# MainBoard-20221122.net
KiCad netlist of a schematic drawn in Altium Designer
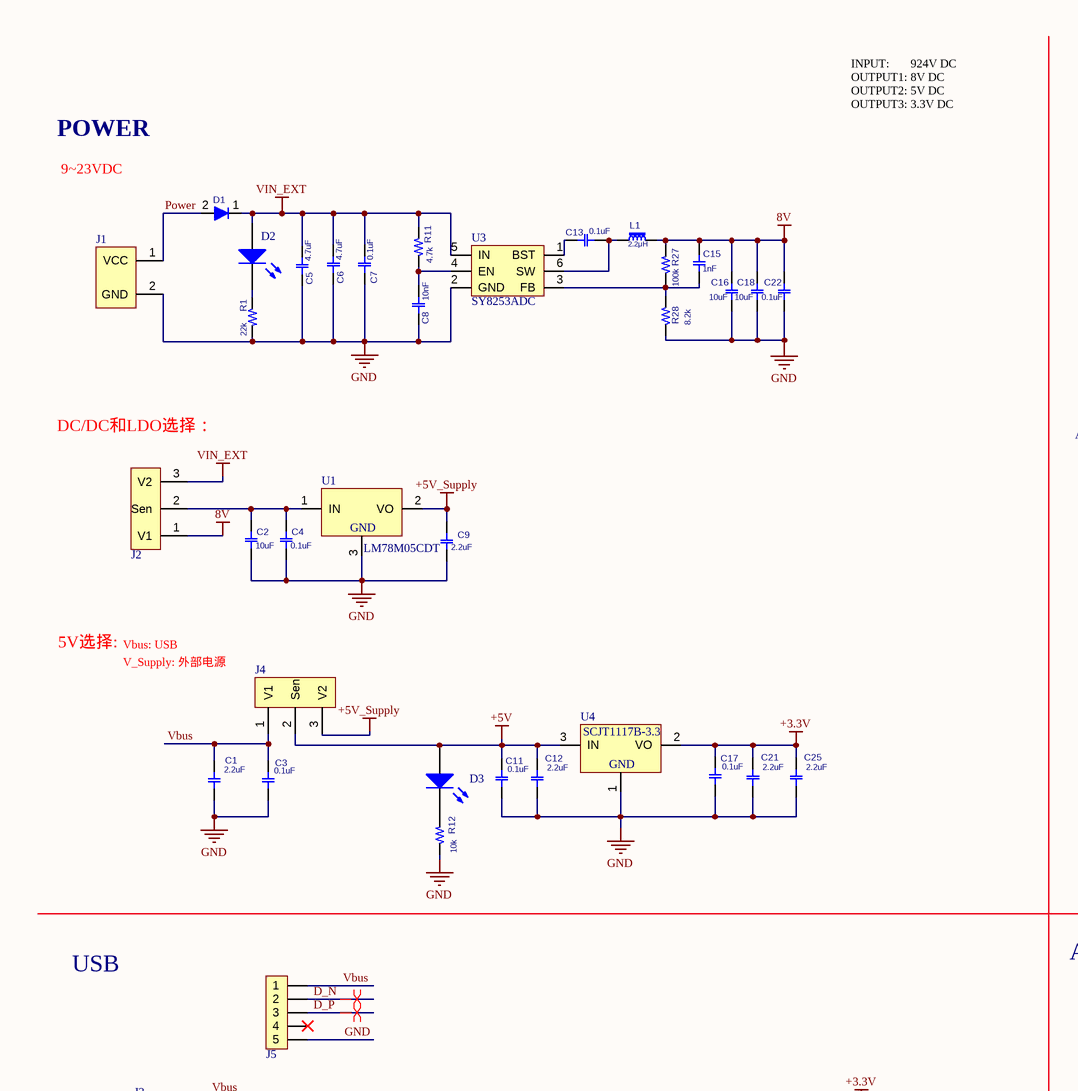
[diagram p0: MainBoard-20221122.SchDoc, top left]
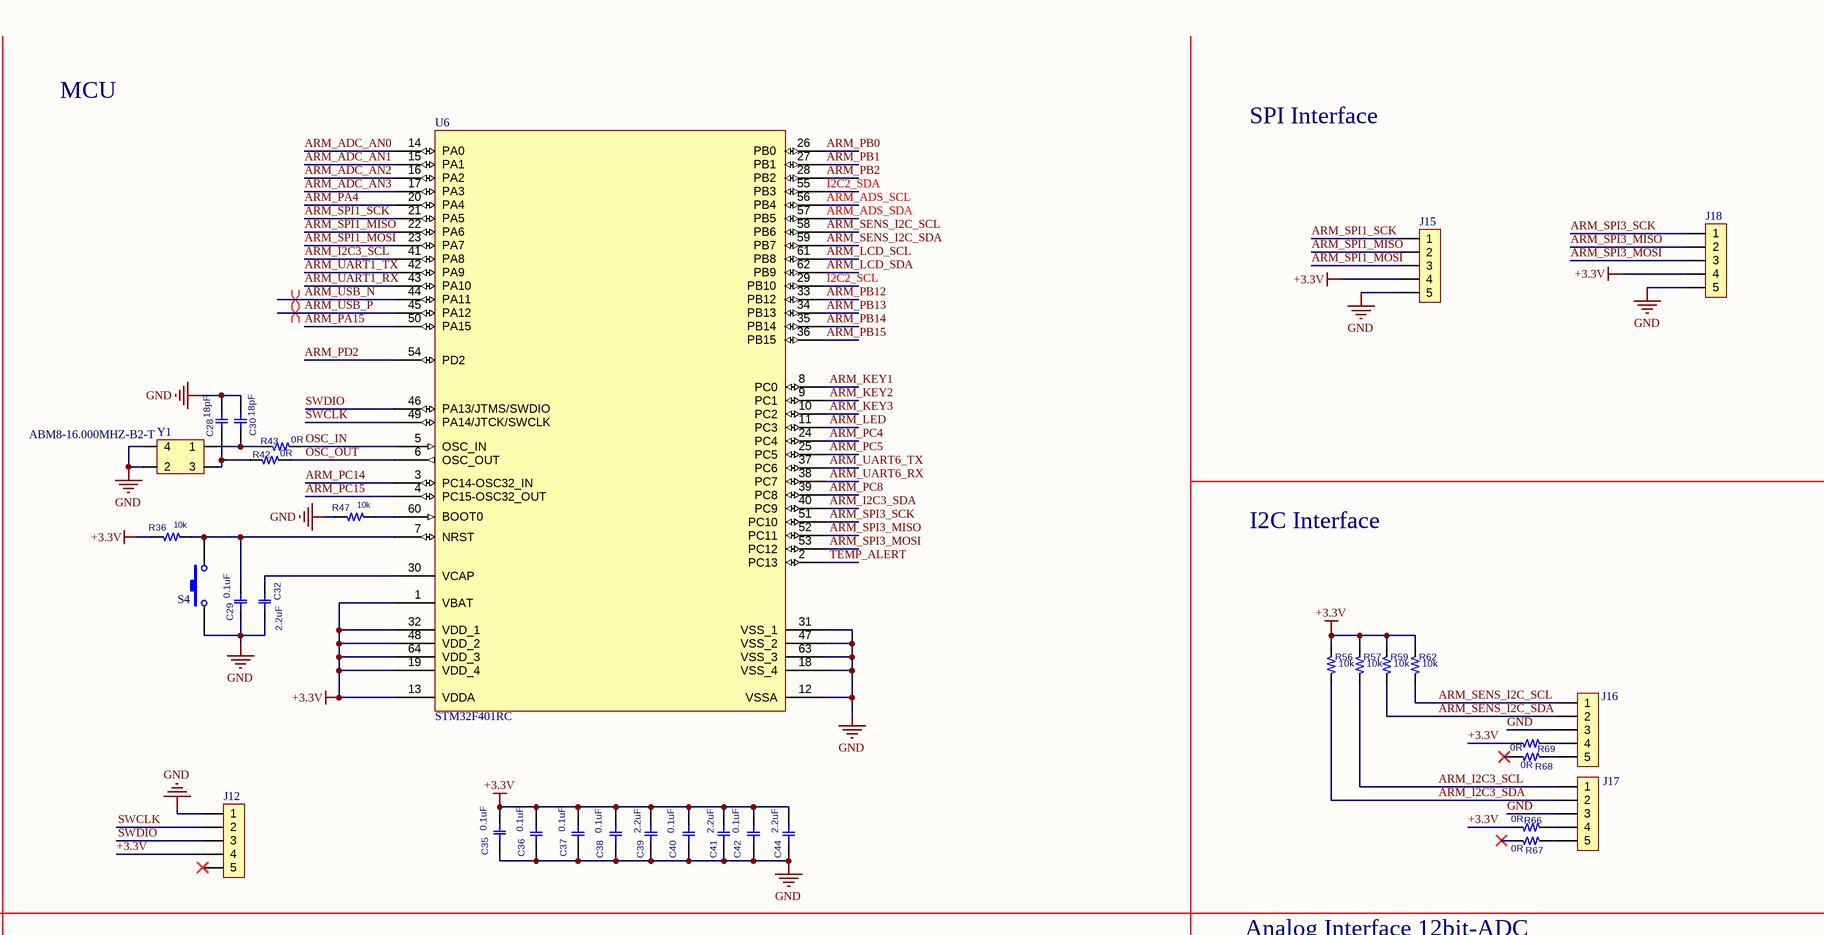
[diagram p1: MainBoard-20221122.SchDoc, top right]
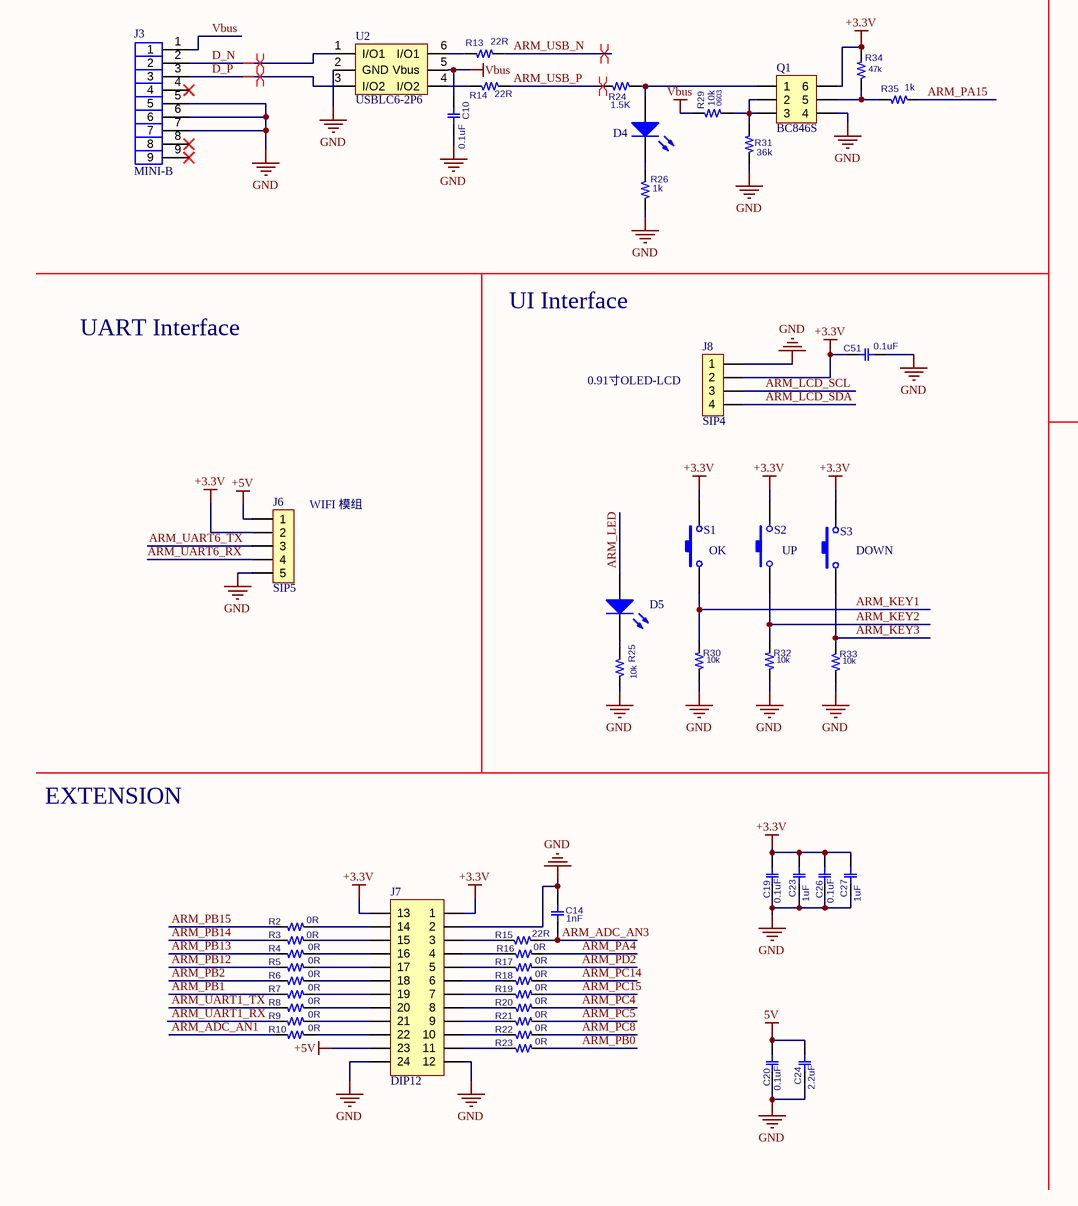
[diagram p2: MainBoard-20221122.SchDoc, bottom left]
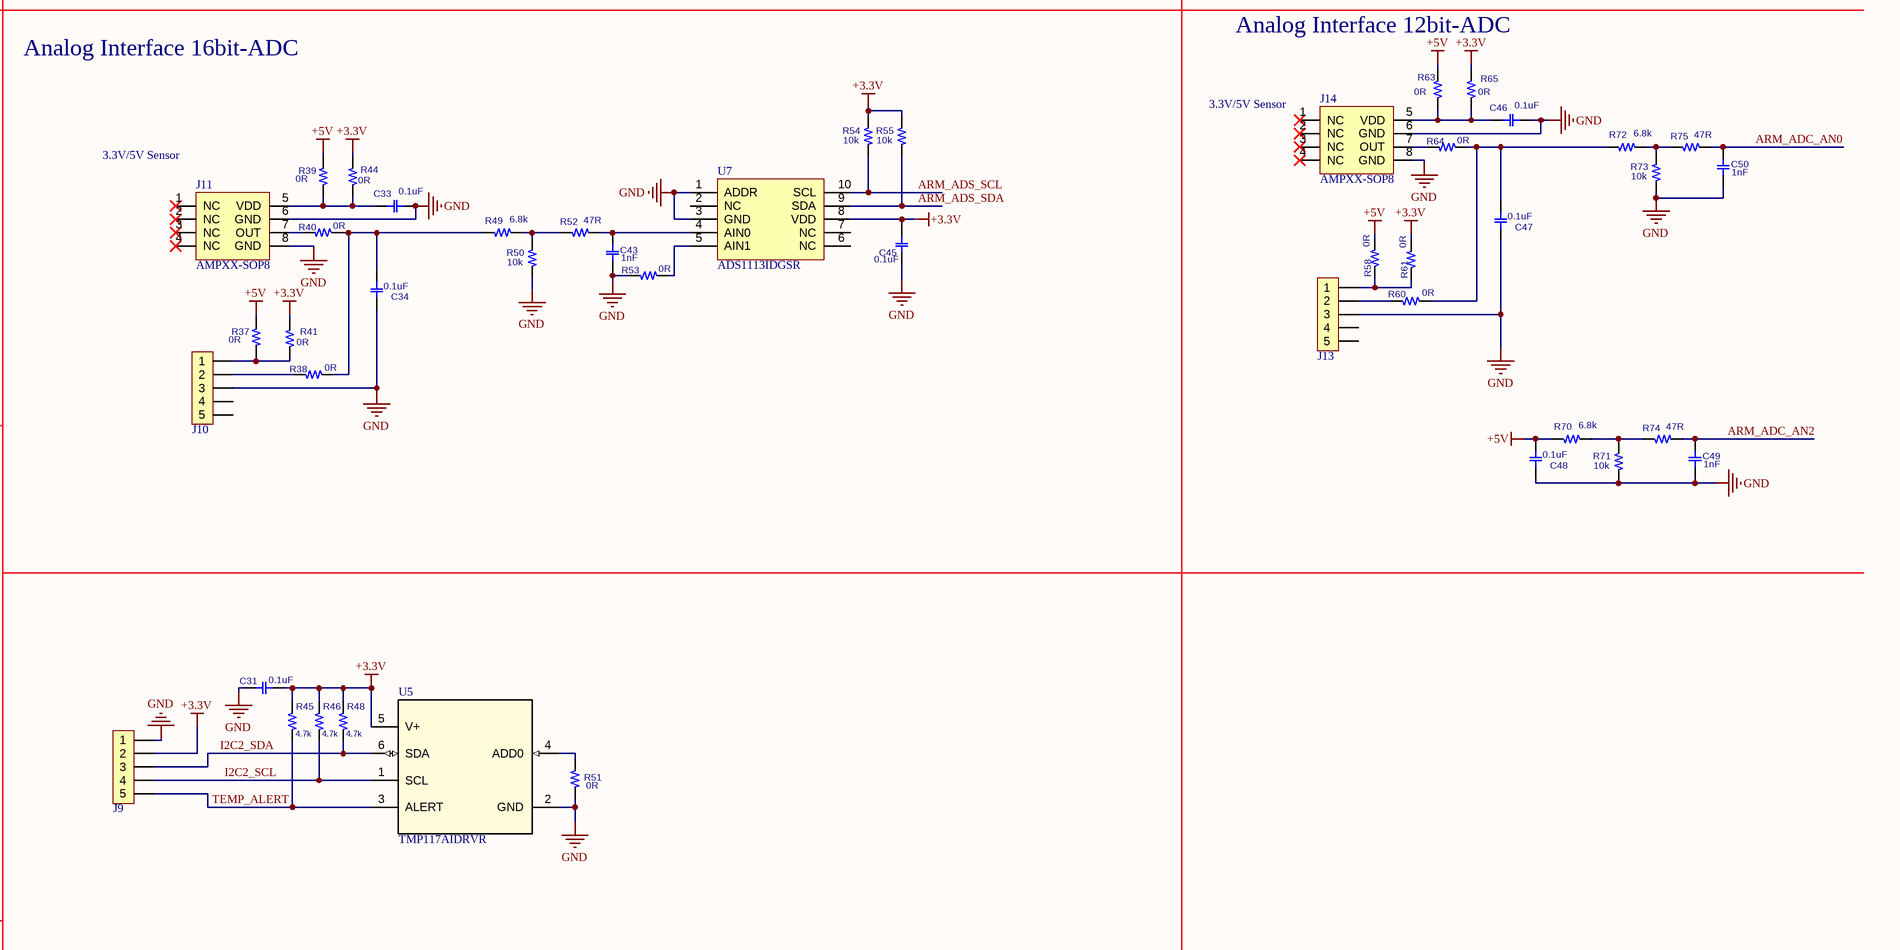
[diagram p3: MainBoard-20221122.SchDoc, bottom right]

(export (version "E")
  (design (tool "Eeschema 10.0.6"))
  (components
    (comp (ref "C1")
      (value "2.2uF")
      (footprint "SMD-C-0603")
      (description "CAP MLCC 1uF 6.3V X7R 20% 0603 AEC-Q200")
      (fields
        (field (name "MANUFACTURER PART NUMBER") "JMK107B7105MAHT")
        (field (name "MANUFACTURER") "TAIYO")
      )
      (libsource (lib "LIB-CASCO-DATA-SMD") (part "SMD-C-JMK107B7105MAHT"))
    )
    (comp (ref "C2")
      (value "10uF")
      (footprint "SMD-C-0805")
      (description "CAP MLCC 0.1uF 35V X5R 20% 0603 AEC-Q200")
      (fields
        (field (name "MANUFACTURER PART NUMBER") "GMK107BJ104MAHT")
        (field (name "MANUFACTURER") "TAIYO")
      )
      (libsource (lib "LIB-CASCO-DATA-SMD") (part "SMD-C-GMK107BJ104MAHT"))
    )
    (comp (ref "C3")
      (value "0.1uF")
      (footprint "SMD-C-0603")
      (description "CAP MLCC 0.1uF 35V X5R 20% 0603 AEC-Q200")
      (fields
        (field (name "MANUFACTURER PART NUMBER") "GMK107BJ104MAHT")
        (field (name "MANUFACTURER") "TAIYO")
      )
      (libsource (lib "LIB-CASCO-DATA-SMD") (part "SMD-C-GMK107BJ104MAHT"))
    )
    (comp (ref "C4")
      (value "0.1uF")
      (footprint "SMD-C-0603")
      (description "CAP MLCC 0.1uF 35V X5R 20% 0603 AEC-Q200")
      (fields
        (field (name "MANUFACTURER PART NUMBER") "GMK107BJ104MAHT")
        (field (name "MANUFACTURER") "TAIYO")
      )
      (libsource (lib "LIB-CASCO-DATA-SMD") (part "SMD-C-GMK107BJ104MAHT"))
    )
    (comp (ref "C5")
      (value "4.7uF")
      (footprint "SMD-C-1206")
      (description "CAP MLCC 0.1uF 35V X5R 20% 0603 AEC-Q200")
      (fields
        (field (name "MANUFACTURER PART NUMBER") "GMK107BJ104MAHT")
        (field (name "MANUFACTURER") "TAIYO")
      )
      (libsource (lib "LIB-CASCO-DATA-SMD") (part "SMD-C-GMK107BJ104MAHT"))
    )
    (comp (ref "C6")
      (value "4.7uF")
      (footprint "SMD-C-1206")
      (description "CAP MLCC 0.1uF 35V X5R 20% 0603 AEC-Q200")
      (fields
        (field (name "MANUFACTURER PART NUMBER") "GMK107BJ104MAHT")
        (field (name "MANUFACTURER") "TAIYO")
      )
      (libsource (lib "LIB-CASCO-DATA-SMD") (part "SMD-C-GMK107BJ104MAHT"))
    )
    (comp (ref "C7")
      (value "0.1uF")
      (footprint "SMD-C-0603")
      (description "CAP MLCC 0.1uF 35V X5R 20% 0603 AEC-Q200")
      (fields
        (field (name "MANUFACTURER PART NUMBER") "GMK107BJ104MAHT")
        (field (name "MANUFACTURER") "TAIYO")
      )
      (libsource (lib "LIB-CASCO-DATA-SMD") (part "SMD-C-GMK107BJ104MAHT"))
    )
    (comp (ref "C8")
      (value "10nF")
      (footprint "SMD-C-0603")
      (description "CAP MLCC 0.1uF 35V X5R 20% 0603 AEC-Q200")
      (fields
        (field (name "MANUFACTURER PART NUMBER") "GMK107BJ104MAHT")
        (field (name "MANUFACTURER") "TAIYO")
      )
      (libsource (lib "LIB-CASCO-DATA-SMD") (part "SMD-C-GMK107BJ104MAHT"))
    )
    (comp (ref "C9")
      (value "2.2uF")
      (footprint "SMD-C-0603")
      (description "CAP MLCC 0.1uF 35V X5R 20% 0603 AEC-Q200")
      (fields
        (field (name "MANUFACTURER PART NUMBER") "GMK107BJ104MAHT")
        (field (name "MANUFACTURER") "TAIYO")
      )
      (libsource (lib "LIB-CASCO-DATA-SMD") (part "SMD-C-GMK107BJ104MAHT"))
    )
    (comp (ref "C10")
      (value "0.1uF")
      (footprint "SMD-C-0603")
      (description "CAP MLCC 0.1uF 35V X5R 20% 0603 AEC-Q200")
      (fields
        (field (name "MANUFACTURER PART NUMBER") "GMK107BJ104MAHT")
        (field (name "MANUFACTURER") "TAIYO")
      )
      (libsource (lib "LIB-CASCO-DATA-SMD") (part "SMD-C-GMK107BJ104MAHT"))
    )
    (comp (ref "C11")
      (value "0.1uF")
      (footprint "SMD-C-0603")
      (description "CAP MLCC 0.1uF 35V X5R 20% 0603 AEC-Q200")
      (fields
        (field (name "MANUFACTURER PART NUMBER") "GMK107BJ104MAHT")
        (field (name "MANUFACTURER") "TAIYO")
      )
      (libsource (lib "LIB-CASCO-DATA-SMD") (part "SMD-C-GMK107BJ104MAHT"))
    )
    (comp (ref "C12")
      (value "2.2uF")
      (footprint "SMD-C-0603")
      (description "CAP MLCC 1uF 6.3V X7R 20% 0603 AEC-Q200")
      (fields
        (field (name "MANUFACTURER PART NUMBER") "JMK107B7105MAHT")
        (field (name "MANUFACTURER") "TAIYO")
      )
      (libsource (lib "LIB-CASCO-DATA-SMD") (part "SMD-C-JMK107B7105MAHT"))
    )
    (comp (ref "C13")
      (value "0.1uF")
      (footprint "SMD-C-0603")
      (description "CAP MLCC 0.1uF 35V X5R 20% 0603 AEC-Q200")
      (fields
        (field (name "MANUFACTURER PART NUMBER") "GMK107BJ104MAHT")
        (field (name "MANUFACTURER") "TAIYO")
      )
      (libsource (lib "LIB-CASCO-DATA-SMD") (part "SMD-C-GMK107BJ104MAHT"))
    )
    (comp (ref "C14")
      (value "1nF")
      (footprint "SMD-C-0603")
      (description "CAP MLCC 0.1uF 35V X5R 20% 0603 AEC-Q200")
      (fields
        (field (name "MANUFACTURER PART NUMBER") "GMK107BJ104MAHT")
        (field (name "MANUFACTURER") "TAIYO")
      )
      (libsource (lib "LIB-CASCO-DATA-SMD") (part "SMD-C-GMK107BJ104MAHT"))
    )
    (comp (ref "C15")
      (value "1nF")
      (footprint "SMD-C-0603")
      (description "CAP MLCC 0.1uF 35V X5R 20% 0603 AEC-Q200")
      (fields
        (field (name "MANUFACTURER PART NUMBER") "GMK107BJ104MAHT")
        (field (name "MANUFACTURER") "TAIYO")
      )
      (libsource (lib "LIB-CASCO-DATA-SMD") (part "SMD-C-GMK107BJ104MAHT"))
    )
    (comp (ref "C16")
      (value "10uF")
      (footprint "SMD-C-0805")
      (description "CAP MLCC 0.1uF 35V X5R 20% 0603 AEC-Q200")
      (fields
        (field (name "MANUFACTURER PART NUMBER") "GMK107BJ104MAHT")
        (field (name "MANUFACTURER") "TAIYO")
      )
      (libsource (lib "LIB-CASCO-DATA-SMD") (part "SMD-C-GMK107BJ104MAHT"))
    )
    (comp (ref "C17")
      (value "0.1uF")
      (footprint "SMD-C-0603")
      (description "CAP MLCC 0.1uF 35V X5R 20% 0603 AEC-Q200")
      (fields
        (field (name "MANUFACTURER PART NUMBER") "GMK107BJ104MAHT")
        (field (name "MANUFACTURER") "TAIYO")
      )
      (libsource (lib "LIB-CASCO-DATA-SMD") (part "SMD-C-GMK107BJ104MAHT"))
    )
    (comp (ref "C18")
      (value "10uF")
      (footprint "SMD-C-0805")
      (description "CAP MLCC 0.1uF 35V X5R 20% 0603 AEC-Q200")
      (fields
        (field (name "MANUFACTURER PART NUMBER") "GMK107BJ104MAHT")
        (field (name "MANUFACTURER") "TAIYO")
      )
      (libsource (lib "LIB-CASCO-DATA-SMD") (part "SMD-C-GMK107BJ104MAHT"))
    )
    (comp (ref "C19")
      (value "0.1uF")
      (footprint "SMD-C-0603")
      (description "CAP MLCC 0.1uF 35V X5R 20% 0603 AEC-Q200")
      (fields
        (field (name "MANUFACTURER PART NUMBER") "GMK107BJ104MAHT")
        (field (name "MANUFACTURER") "TAIYO")
      )
      (libsource (lib "LIB-CASCO-DATA-SMD") (part "SMD-C-GMK107BJ104MAHT"))
    )
    (comp (ref "C20")
      (value "0.1uF")
      (footprint "SMD-C-0603")
      (description "CAP MLCC 0.1uF 35V X5R 20% 0603 AEC-Q200")
      (fields
        (field (name "MANUFACTURER PART NUMBER") "GMK107BJ104MAHT")
        (field (name "MANUFACTURER") "TAIYO")
      )
      (libsource (lib "LIB-CASCO-DATA-SMD") (part "SMD-C-GMK107BJ104MAHT"))
    )
    (comp (ref "C21")
      (value "2.2uF")
      (footprint "SMD-C-0603")
      (description "CAP MLCC 1uF 6.3V X7R 20% 0603 AEC-Q200")
      (fields
        (field (name "MANUFACTURER PART NUMBER") "JMK107B7105MAHT")
        (field (name "MANUFACTURER") "TAIYO")
      )
      (libsource (lib "LIB-CASCO-DATA-SMD") (part "SMD-C-JMK107B7105MAHT"))
    )
    (comp (ref "C22")
      (value "0.1uF")
      (footprint "SMD-C-0603")
      (description "CAP MLCC 0.1uF 35V X5R 20% 0603 AEC-Q200")
      (fields
        (field (name "MANUFACTURER PART NUMBER") "GMK107BJ104MAHT")
        (field (name "MANUFACTURER") "TAIYO")
      )
      (libsource (lib "LIB-CASCO-DATA-SMD") (part "SMD-C-GMK107BJ104MAHT"))
    )
    (comp (ref "C23")
      (value "1uF")
      (footprint "SMD-C-0603")
      (description "CAP MLCC 0.1uF 35V X5R 20% 0603 AEC-Q200")
      (fields
        (field (name "MANUFACTURER PART NUMBER") "GMK107BJ104MAHT")
        (field (name "MANUFACTURER") "TAIYO")
      )
      (libsource (lib "LIB-CASCO-DATA-SMD") (part "SMD-C-GMK107BJ104MAHT"))
    )
    (comp (ref "C24")
      (value "2.2uF")
      (footprint "SMD-C-0603")
      (description "CAP MLCC 0.1uF 35V X5R 20% 0603 AEC-Q200")
      (fields
        (field (name "MANUFACTURER PART NUMBER") "GMK107BJ104MAHT")
        (field (name "MANUFACTURER") "TAIYO")
      )
      (libsource (lib "LIB-CASCO-DATA-SMD") (part "SMD-C-GMK107BJ104MAHT"))
    )
    (comp (ref "C25")
      (value "2.2uF")
      (footprint "SMD-C-0603")
      (description "CAP MLCC 1uF 6.3V X7R 20% 0603 AEC-Q200")
      (fields
        (field (name "MANUFACTURER PART NUMBER") "JMK107B7105MAHT")
        (field (name "MANUFACTURER") "TAIYO")
      )
      (libsource (lib "LIB-CASCO-DATA-SMD") (part "SMD-C-JMK107B7105MAHT"))
    )
    (comp (ref "C26")
      (value "0.1uF")
      (footprint "SMD-C-0603")
      (description "CAP MLCC 0.1uF 35V X5R 20% 0603 AEC-Q200")
      (fields
        (field (name "MANUFACTURER PART NUMBER") "GMK107BJ104MAHT")
        (field (name "MANUFACTURER") "TAIYO")
      )
      (libsource (lib "LIB-CASCO-DATA-SMD") (part "SMD-C-GMK107BJ104MAHT"))
    )
    (comp (ref "C27")
      (value "1uF")
      (footprint "SMD-C-0603")
      (description "CAP MLCC 0.1uF 35V X5R 20% 0603 AEC-Q200")
      (fields
        (field (name "MANUFACTURER PART NUMBER") "GMK107BJ104MAHT")
        (field (name "MANUFACTURER") "TAIYO")
      )
      (libsource (lib "LIB-CASCO-DATA-SMD") (part "SMD-C-GMK107BJ104MAHT"))
    )
    (comp (ref "C28")
      (value "18pF")
      (footprint "SMD-C-0603")
      (description "CAP MLCC 0.1uF 35V X5R 20% 0603 AEC-Q200")
      (fields
        (field (name "MANUFACTURER PART NUMBER") "GMK107BJ104MAHT")
        (field (name "MANUFACTURER") "TAIYO")
      )
      (libsource (lib "LIB-CASCO-DATA-SMD") (part "SMD-C-GMK107BJ104MAHT"))
    )
    (comp (ref "C29")
      (value "0.1uF")
      (footprint "SMD-C-0603")
      (description "CAP MLCC 0.1uF 35V X5R 20% 0603 AEC-Q200")
      (fields
        (field (name "MANUFACTURER PART NUMBER") "GMK107BJ104MAHT")
        (field (name "MANUFACTURER") "TAIYO")
      )
      (libsource (lib "LIB-CASCO-DATA-SMD") (part "SMD-C-GMK107BJ104MAHT"))
    )
    (comp (ref "C30")
      (value "18pF")
      (footprint "SMD-C-0603")
      (description "CAP MLCC 0.1uF 35V X5R 20% 0603 AEC-Q200")
      (fields
        (field (name "MANUFACTURER PART NUMBER") "GMK107BJ104MAHT")
        (field (name "MANUFACTURER") "TAIYO")
      )
      (libsource (lib "LIB-CASCO-DATA-SMD") (part "SMD-C-GMK107BJ104MAHT"))
    )
    (comp (ref "C31")
      (value "0.1uF")
      (footprint "SMD-C-0603")
      (description "CAP MLCC 0.1uF 35V X5R 20% 0603 AEC-Q200")
      (fields
        (field (name "MANUFACTURER PART NUMBER") "GMK107BJ104MAHT")
        (field (name "MANUFACTURER") "TAIYO")
      )
      (libsource (lib "LIB-CASCO-DATA-SMD") (part "SMD-C-GMK107BJ104MAHT"))
    )
    (comp (ref "C32")
      (value "2.2uF")
      (footprint "SMD-C-0603")
      (description "CAP MLCC 1uF 6.3V X7R 20% 0603 AEC-Q200")
      (fields
        (field (name "MANUFACTURER PART NUMBER") "JMK107B7105MAHT")
        (field (name "MANUFACTURER") "TAIYO")
      )
      (libsource (lib "LIB-CASCO-DATA-SMD") (part "SMD-C-JMK107B7105MAHT"))
    )
    (comp (ref "C33")
      (value "0.1uF")
      (footprint "SMD-C-0603")
      (description "CAP MLCC 0.1uF 35V X5R 20% 0603 AEC-Q200")
      (fields
        (field (name "MANUFACTURER PART NUMBER") "GMK107BJ104MAHT")
        (field (name "MANUFACTURER") "TAIYO")
      )
      (libsource (lib "LIB-CASCO-DATA-SMD") (part "SMD-C-GMK107BJ104MAHT"))
    )
    (comp (ref "C34")
      (value "0.1uF")
      (footprint "SMD-C-0603")
      (description "CAP MLCC 0.1uF 35V X5R 20% 0603 AEC-Q200")
      (fields
        (field (name "MANUFACTURER PART NUMBER") "GMK107BJ104MAHT")
        (field (name "MANUFACTURER") "TAIYO")
      )
      (libsource (lib "LIB-CASCO-DATA-SMD") (part "SMD-C-GMK107BJ104MAHT"))
    )
    (comp (ref "C35")
      (value "0.1uF")
      (footprint "SMD-C-0603")
      (description "CAP MLCC 0.1uF 35V X5R 20% 0603 AEC-Q200")
      (fields
        (field (name "MANUFACTURER PART NUMBER") "GMK107BJ104MAHT")
        (field (name "MANUFACTURER") "TAIYO")
      )
      (libsource (lib "LIB-CASCO-DATA-SMD") (part "SMD-C-GMK107BJ104MAHT"))
    )
    (comp (ref "C36")
      (value "0.1uF")
      (footprint "SMD-C-0603")
      (description "CAP MLCC 0.1uF 35V X5R 20% 0603 AEC-Q200")
      (fields
        (field (name "MANUFACTURER PART NUMBER") "GMK107BJ104MAHT")
        (field (name "MANUFACTURER") "TAIYO")
      )
      (libsource (lib "LIB-CASCO-DATA-SMD") (part "SMD-C-GMK107BJ104MAHT"))
    )
    (comp (ref "C37")
      (value "0.1uF")
      (footprint "SMD-C-0603")
      (description "CAP MLCC 0.1uF 35V X5R 20% 0603 AEC-Q200")
      (fields
        (field (name "MANUFACTURER PART NUMBER") "GMK107BJ104MAHT")
        (field (name "MANUFACTURER") "TAIYO")
      )
      (libsource (lib "LIB-CASCO-DATA-SMD") (part "SMD-C-GMK107BJ104MAHT"))
    )
    (comp (ref "C38")
      (value "0.1uF")
      (footprint "SMD-C-0603")
      (description "CAP MLCC 0.1uF 35V X5R 20% 0603 AEC-Q200")
      (fields
        (field (name "MANUFACTURER PART NUMBER") "GMK107BJ104MAHT")
        (field (name "MANUFACTURER") "TAIYO")
      )
      (libsource (lib "LIB-CASCO-DATA-SMD") (part "SMD-C-GMK107BJ104MAHT"))
    )
    (comp (ref "C39")
      (value "2.2uF")
      (footprint "SMD-C-0603")
      (description "CAP MLCC 1uF 6.3V X7R 20% 0603 AEC-Q200")
      (fields
        (field (name "MANUFACTURER PART NUMBER") "JMK107B7105MAHT")
        (field (name "MANUFACTURER") "TAIYO")
      )
      (libsource (lib "LIB-CASCO-DATA-SMD") (part "SMD-C-JMK107B7105MAHT"))
    )
    (comp (ref "C40")
      (value "0.1uF")
      (footprint "SMD-C-0603")
      (description "CAP MLCC 0.1uF 35V X5R 20% 0603 AEC-Q200")
      (fields
        (field (name "MANUFACTURER PART NUMBER") "GMK107BJ104MAHT")
        (field (name "MANUFACTURER") "TAIYO")
      )
      (libsource (lib "LIB-CASCO-DATA-SMD") (part "SMD-C-GMK107BJ104MAHT"))
    )
    (comp (ref "C41")
      (value "2.2uF")
      (footprint "SMD-C-0603")
      (description "CAP MLCC 1uF 6.3V X7R 20% 0603 AEC-Q200")
      (fields
        (field (name "MANUFACTURER PART NUMBER") "JMK107B7105MAHT")
        (field (name "MANUFACTURER") "TAIYO")
      )
      (libsource (lib "LIB-CASCO-DATA-SMD") (part "SMD-C-JMK107B7105MAHT"))
    )
    (comp (ref "C42")
      (value "0.1uF")
      (footprint "SMD-C-0603")
      (description "CAP MLCC 0.1uF 35V X5R 20% 0603 AEC-Q200")
      (fields
        (field (name "MANUFACTURER PART NUMBER") "GMK107BJ104MAHT")
        (field (name "MANUFACTURER") "TAIYO")
      )
      (libsource (lib "LIB-CASCO-DATA-SMD") (part "SMD-C-GMK107BJ104MAHT"))
    )
    (comp (ref "C43")
      (value "1nF")
      (footprint "SMD-C-0603")
      (description "CAP MLCC 0.1uF 35V X5R 20% 0603 AEC-Q200")
      (fields
        (field (name "MANUFACTURER PART NUMBER") "GMK107BJ104MAHT")
        (field (name "MANUFACTURER") "TAIYO")
      )
      (libsource (lib "LIB-CASCO-DATA-SMD") (part "SMD-C-GMK107BJ104MAHT"))
    )
    (comp (ref "C44")
      (value "2.2uF")
      (footprint "SMD-C-0603")
      (description "CAP MLCC 1uF 6.3V X7R 20% 0603 AEC-Q200")
      (fields
        (field (name "MANUFACTURER PART NUMBER") "JMK107B7105MAHT")
        (field (name "MANUFACTURER") "TAIYO")
      )
      (libsource (lib "LIB-CASCO-DATA-SMD") (part "SMD-C-JMK107B7105MAHT"))
    )
    (comp (ref "C45")
      (value "0.1uF")
      (footprint "SMD-C-0603")
      (description "CAP MLCC 0.1uF 35V X5R 20% 0603 AEC-Q200")
      (fields
        (field (name "MANUFACTURER PART NUMBER") "GMK107BJ104MAHT")
        (field (name "MANUFACTURER") "TAIYO")
      )
      (libsource (lib "LIB-CASCO-DATA-SMD") (part "SMD-C-GMK107BJ104MAHT"))
    )
    (comp (ref "C46")
      (value "0.1uF")
      (footprint "SMD-C-0603")
      (description "CAP MLCC 0.1uF 35V X5R 20% 0603 AEC-Q200")
      (fields
        (field (name "MANUFACTURER PART NUMBER") "GMK107BJ104MAHT")
        (field (name "MANUFACTURER") "TAIYO")
      )
      (libsource (lib "LIB-CASCO-DATA-SMD") (part "SMD-C-GMK107BJ104MAHT"))
    )
    (comp (ref "C47")
      (value "0.1uF")
      (footprint "SMD-C-0603")
      (description "CAP MLCC 0.1uF 35V X5R 20% 0603 AEC-Q200")
      (fields
        (field (name "MANUFACTURER PART NUMBER") "GMK107BJ104MAHT")
        (field (name "MANUFACTURER") "TAIYO")
      )
      (libsource (lib "LIB-CASCO-DATA-SMD") (part "SMD-C-GMK107BJ104MAHT"))
    )
    (comp (ref "C48")
      (value "0.1uF")
      (footprint "SMD-C-0603")
      (description "CAP MLCC 0.1uF 35V X5R 20% 0603 AEC-Q200")
      (fields
        (field (name "MANUFACTURER PART NUMBER") "GMK107BJ104MAHT")
        (field (name "MANUFACTURER") "TAIYO")
      )
      (libsource (lib "LIB-CASCO-DATA-SMD") (part "SMD-C-GMK107BJ104MAHT"))
    )
    (comp (ref "C49")
      (value "1nF")
      (footprint "SMD-C-0603")
      (description "CAP MLCC 0.1uF 35V X5R 20% 0603 AEC-Q200")
      (fields
        (field (name "MANUFACTURER PART NUMBER") "GMK107BJ104MAHT")
        (field (name "MANUFACTURER") "TAIYO")
      )
      (libsource (lib "LIB-CASCO-DATA-SMD") (part "SMD-C-GMK107BJ104MAHT"))
    )
    (comp (ref "C50")
      (value "1nF")
      (footprint "SMD-C-0603")
      (description "CAP MLCC 0.1uF 35V X5R 20% 0603 AEC-Q200")
      (fields
        (field (name "MANUFACTURER PART NUMBER") "GMK107BJ104MAHT")
        (field (name "MANUFACTURER") "TAIYO")
      )
      (libsource (lib "LIB-CASCO-DATA-SMD") (part "SMD-C-GMK107BJ104MAHT"))
    )
    (comp (ref "C51")
      (value "0.1uF")
      (footprint "SMD-C-0603")
      (description "CAP MLCC 0.1uF 35V X5R 20% 0603 AEC-Q200")
      (fields
        (field (name "MANUFACTURER PART NUMBER") "GMK107BJ104MAHT")
        (field (name "MANUFACTURER") "TAIYO")
      )
      (libsource (lib "LIB-CASCO-DATA-SMD") (part "SMD-C-GMK107BJ104MAHT"))
    )
    (comp (ref "D1")
      (value "SK54BL")
      (footprint "SMD-D-SMA")
      (description "DIODE SCHOTTKY 40V 5A SMB")
      (fields (field (name "MANUFACTURER") "PANJIT") (field (name "MANUFACTURER PART NUMBER") "D"))
      (libsource (lib "*") (part "SMD-D-SK54BL"))
    )
    (comp (ref "D2")
      (value "LED1")
      (footprint "LED0603")
      (description "Typical RED GaAs LED")
      (fields (field (name "PUBLISHER") "Altium Limited"))
      (libsource (lib "Miscellaneous Devices") (part "LED1"))
    )
    (comp (ref "D3")
      (value "LED1")
      (footprint "LED0603")
      (description "Typical RED GaAs LED")
      (fields (field (name "PUBLISHER") "Altium Limited"))
      (libsource (lib "Miscellaneous Devices") (part "LED1"))
    )
    (comp (ref "D4")
      (value "LED1")
      (footprint "LED0603")
      (description "Typical RED GaAs LED")
      (fields (field (name "PUBLISHER") "Altium Limited"))
      (libsource (lib "Miscellaneous Devices") (part "LED1"))
    )
    (comp (ref "D5")
      (value "LED1")
      (footprint "LED0603")
      (description "Typical RED GaAs LED")
      (fields (field (name "PUBLISHER") "Altium Limited"))
      (libsource (lib "Miscellaneous Devices") (part "LED1"))
    )
    (comp (ref "J1") (value "SIP2") (footprint "SIP2") (libsource (lib "Schlib1") (part "SIP2")))
    (comp (ref "J2") (value "SIP3-3") (footprint "SIP3") (libsource (lib "") (part "SIP3-3_1")))
    (comp (ref "J3") (value "MINI-B") (footprint "usb") (libsource (lib "Schlib1") (part "MINI-B")))
    (comp (ref "J4") (value "SIP3-3") (footprint "SIP3") (libsource (lib "Schlib1") (part "SIP3-3")))
    (comp (ref "J5") (value "SIP5") (footprint "SIP5") (libsource (lib "") (part "SIP5_1")))
    (comp (ref "J6") (value "SIP5") (footprint "SIP5") (libsource (lib "Schlib1") (part "SIP5")))
    (comp (ref "J7") (value "DIP12") (footprint "DIP12") (libsource (lib "Schlib1") (part "DIP12")))
    (comp (ref "J8") (value "SIP4") (footprint "OLED") (libsource (lib "Schlib1") (part "SIP4")))
    (comp (ref "J9") (value "SIP5") (footprint "SIP5") (libsource (lib "") (part "SIP5_1")))
    (comp (ref "J10") (value "SIP5") (footprint "SIP5") (libsource (lib "") (part "SIP5_1")))
    (comp (ref "J11")
      (value "AMPXX-SOP8")
      (footprint "AMP8220-L")
      (libsource (lib "Schlib1") (part "AMP8220"))
    )
    (comp (ref "J12") (value "SIP5") (footprint "SIP5") (libsource (lib "Schlib1") (part "SIP5")))
    (comp (ref "J13") (value "SIP5") (footprint "SIP5") (libsource (lib "") (part "SIP5_1")))
    (comp (ref "J14")
      (value "AMPXX-SOP8")
      (footprint "AMP8220-L")
      (libsource (lib "Schlib1") (part "AMP8220"))
    )
    (comp (ref "J15") (value "SIP5") (footprint "SIP5") (libsource (lib "Schlib1") (part "SIP5")))
    (comp (ref "J16") (value "SIP5") (footprint "SIP5") (libsource (lib "Schlib1") (part "SIP5")))
    (comp (ref "J17") (value "SIP5") (footprint "SIP5") (libsource (lib "Schlib1") (part "SIP5")))
    (comp (ref "J18") (value "SIP5") (footprint "SIP5") (libsource (lib "Schlib1") (part "SIP5")))
    (comp (ref "L1")
      (value "YZL-8040-6R8M-LF")
      (footprint "SMD-L-YZL-8040-8x8x4")
      (description "INDUCTOR 6.8μH Isat 4A ±20%")
      (fields
        (field (name "MANUFACTURER") "YLZ (益泽联)")
        (field (name "TOLERANCE") "±20%")
        (field (name "INDUCTANCE") "2.2μH")
      )
      (libsource (lib "LIB-CASCO-DATA-SMD") (part "SMD-L-YZL-8040-6R8M-LF"))
    )
    (comp (ref "Q1") (value "BC846S") (footprint "SOT363") (libsource (lib "Schlib1") (part "BC846S")))
    (comp (ref "R1")
      (value "22k")
      (footprint "SMD-R-0603")
      (description "603 AEC-Q200")
      (fields
        (field (name "MANUFACTURER") "VIKING")
        (field (name "MANUFACTURER PART NUMBER") "CR-03FA7--100R")
      )
      (libsource (lib "LIB-CASCO-DATA-SMD") (part "SMD-R-CR-03FA7--100R"))
    )
    (comp (ref "R2")
      (value "0R")
      (footprint "SMD-R-0603")
      (description "603 AEC-Q200")
      (fields
        (field (name "MANUFACTURER") "VIKING")
        (field (name "MANUFACTURER PART NUMBER") "CR-03FA7--100R")
      )
      (libsource (lib "LIB-CASCO-DATA-SMD") (part "SMD-R-CR-03FA7--100R"))
    )
    (comp (ref "R3")
      (value "0R")
      (footprint "SMD-R-0603")
      (description "603 AEC-Q200")
      (fields
        (field (name "MANUFACTURER") "VIKING")
        (field (name "MANUFACTURER PART NUMBER") "CR-03FA7--100R")
      )
      (libsource (lib "LIB-CASCO-DATA-SMD") (part "SMD-R-CR-03FA7--100R"))
    )
    (comp (ref "R4")
      (value "0R")
      (footprint "SMD-R-0603")
      (description "603 AEC-Q200")
      (fields
        (field (name "MANUFACTURER") "VIKING")
        (field (name "MANUFACTURER PART NUMBER") "CR-03FA7--100R")
      )
      (libsource (lib "LIB-CASCO-DATA-SMD") (part "SMD-R-CR-03FA7--100R"))
    )
    (comp (ref "R5")
      (value "0R")
      (footprint "SMD-R-0603")
      (description "603 AEC-Q200")
      (fields
        (field (name "MANUFACTURER") "VIKING")
        (field (name "MANUFACTURER PART NUMBER") "CR-03FA7--100R")
      )
      (libsource (lib "LIB-CASCO-DATA-SMD") (part "SMD-R-CR-03FA7--100R"))
    )
    (comp (ref "R6")
      (value "0R")
      (footprint "SMD-R-0603")
      (description "603 AEC-Q200")
      (fields
        (field (name "MANUFACTURER") "VIKING")
        (field (name "MANUFACTURER PART NUMBER") "CR-03FA7--100R")
      )
      (libsource (lib "LIB-CASCO-DATA-SMD") (part "SMD-R-CR-03FA7--100R"))
    )
    (comp (ref "R7")
      (value "0R")
      (footprint "SMD-R-0603")
      (description "603 AEC-Q200")
      (fields
        (field (name "MANUFACTURER") "VIKING")
        (field (name "MANUFACTURER PART NUMBER") "CR-03FA7--100R")
      )
      (libsource (lib "LIB-CASCO-DATA-SMD") (part "SMD-R-CR-03FA7--100R"))
    )
    (comp (ref "R8")
      (value "0R")
      (footprint "SMD-R-0603")
      (description "603 AEC-Q200")
      (fields
        (field (name "MANUFACTURER") "VIKING")
        (field (name "MANUFACTURER PART NUMBER") "CR-03FA7--100R")
      )
      (libsource (lib "LIB-CASCO-DATA-SMD") (part "SMD-R-CR-03FA7--100R"))
    )
    (comp (ref "R9")
      (value "0R")
      (footprint "SMD-R-0603")
      (description "603 AEC-Q200")
      (fields
        (field (name "MANUFACTURER") "VIKING")
        (field (name "MANUFACTURER PART NUMBER") "CR-03FA7--100R")
      )
      (libsource (lib "LIB-CASCO-DATA-SMD") (part "SMD-R-CR-03FA7--100R"))
    )
    (comp (ref "R10")
      (value "0R")
      (footprint "SMD-R-0603")
      (description "603 AEC-Q200")
      (fields
        (field (name "MANUFACTURER") "VIKING")
        (field (name "MANUFACTURER PART NUMBER") "CR-03FA7--100R")
      )
      (libsource (lib "LIB-CASCO-DATA-SMD") (part "SMD-R-CR-03FA7--100R"))
    )
    (comp (ref "R11")
      (value "4.7k")
      (footprint "SMD-R-0603")
      (description "603 AEC-Q200")
      (fields
        (field (name "MANUFACTURER") "VIKING")
        (field (name "MANUFACTURER PART NUMBER") "CR-03FA7--100R")
      )
      (libsource (lib "LIB-CASCO-DATA-SMD") (part "SMD-R-CR-03FA7--100R"))
    )
    (comp (ref "R12")
      (value "10k")
      (footprint "SMD-R-0603")
      (description "603 AEC-Q200")
      (fields
        (field (name "MANUFACTURER") "VIKING")
        (field (name "MANUFACTURER PART NUMBER") "CR-03FA7--100R")
      )
      (libsource (lib "LIB-CASCO-DATA-SMD") (part "SMD-R-CR-03FA7--100R"))
    )
    (comp (ref "R13")
      (value "22R")
      (footprint "SMD-R-0603")
      (description "603 AEC-Q200")
      (fields
        (field (name "MANUFACTURER") "VIKING")
        (field (name "MANUFACTURER PART NUMBER") "CR-03FA7--100R")
      )
      (libsource (lib "LIB-CASCO-DATA-SMD") (part "SMD-R-CR-03FA7--100R"))
    )
    (comp (ref "R14")
      (value "22R")
      (footprint "SMD-R-0603")
      (description "603 AEC-Q200")
      (fields
        (field (name "MANUFACTURER") "VIKING")
        (field (name "MANUFACTURER PART NUMBER") "CR-03FA7--100R")
      )
      (libsource (lib "LIB-CASCO-DATA-SMD") (part "SMD-R-CR-03FA7--100R"))
    )
    (comp (ref "R15")
      (value "22R")
      (footprint "SMD-R-0603")
      (description "603 AEC-Q200")
      (fields
        (field (name "MANUFACTURER") "VIKING")
        (field (name "MANUFACTURER PART NUMBER") "CR-03FA7--100R")
      )
      (libsource (lib "LIB-CASCO-DATA-SMD") (part "SMD-R-CR-03FA7--100R"))
    )
    (comp (ref "R16")
      (value "0R")
      (footprint "SMD-R-0603")
      (description "603 AEC-Q200")
      (fields
        (field (name "MANUFACTURER") "VIKING")
        (field (name "MANUFACTURER PART NUMBER") "CR-03FA7--100R")
      )
      (libsource (lib "LIB-CASCO-DATA-SMD") (part "SMD-R-CR-03FA7--100R"))
    )
    (comp (ref "R17")
      (value "0R")
      (footprint "SMD-R-0603")
      (description "603 AEC-Q200")
      (fields
        (field (name "MANUFACTURER") "VIKING")
        (field (name "MANUFACTURER PART NUMBER") "CR-03FA7--100R")
      )
      (libsource (lib "LIB-CASCO-DATA-SMD") (part "SMD-R-CR-03FA7--100R"))
    )
    (comp (ref "R18")
      (value "0R")
      (footprint "SMD-R-0603")
      (description "603 AEC-Q200")
      (fields
        (field (name "MANUFACTURER") "VIKING")
        (field (name "MANUFACTURER PART NUMBER") "CR-03FA7--100R")
      )
      (libsource (lib "LIB-CASCO-DATA-SMD") (part "SMD-R-CR-03FA7--100R"))
    )
    (comp (ref "R19")
      (value "0R")
      (footprint "SMD-R-0603")
      (description "603 AEC-Q200")
      (fields
        (field (name "MANUFACTURER") "VIKING")
        (field (name "MANUFACTURER PART NUMBER") "CR-03FA7--100R")
      )
      (libsource (lib "LIB-CASCO-DATA-SMD") (part "SMD-R-CR-03FA7--100R"))
    )
    (comp (ref "R20")
      (value "0R")
      (footprint "SMD-R-0603")
      (description "603 AEC-Q200")
      (fields
        (field (name "MANUFACTURER") "VIKING")
        (field (name "MANUFACTURER PART NUMBER") "CR-03FA7--100R")
      )
      (libsource (lib "LIB-CASCO-DATA-SMD") (part "SMD-R-CR-03FA7--100R"))
    )
    (comp (ref "R21")
      (value "0R")
      (footprint "SMD-R-0603")
      (description "603 AEC-Q200")
      (fields
        (field (name "MANUFACTURER") "VIKING")
        (field (name "MANUFACTURER PART NUMBER") "CR-03FA7--100R")
      )
      (libsource (lib "LIB-CASCO-DATA-SMD") (part "SMD-R-CR-03FA7--100R"))
    )
    (comp (ref "R22")
      (value "0R")
      (footprint "SMD-R-0603")
      (description "603 AEC-Q200")
      (fields
        (field (name "MANUFACTURER") "VIKING")
        (field (name "MANUFACTURER PART NUMBER") "CR-03FA7--100R")
      )
      (libsource (lib "LIB-CASCO-DATA-SMD") (part "SMD-R-CR-03FA7--100R"))
    )
    (comp (ref "R23")
      (value "0R")
      (footprint "SMD-R-0603")
      (description "603 AEC-Q200")
      (fields
        (field (name "MANUFACTURER") "VIKING")
        (field (name "MANUFACTURER PART NUMBER") "CR-03FA7--100R")
      )
      (libsource (lib "LIB-CASCO-DATA-SMD") (part "SMD-R-CR-03FA7--100R"))
    )
    (comp (ref "R24")
      (value "1.5K")
      (footprint "SMD-R-0603")
      (description "603 AEC-Q200")
      (fields
        (field (name "MANUFACTURER") "VIKING")
        (field (name "MANUFACTURER PART NUMBER") "CR-03FA7--100R")
      )
      (libsource (lib "LIB-CASCO-DATA-SMD") (part "SMD-R-CR-03FA7--100R"))
    )
    (comp (ref "R25")
      (value "10k")
      (footprint "SMD-R-0603")
      (description "603 AEC-Q200")
      (fields
        (field (name "MANUFACTURER") "VIKING")
        (field (name "MANUFACTURER PART NUMBER") "CR-03FA7--100R")
      )
      (libsource (lib "LIB-CASCO-DATA-SMD") (part "SMD-R-CR-03FA7--100R"))
    )
    (comp (ref "R26")
      (value "1k")
      (footprint "SMD-R-0603")
      (description "603 AEC-Q200")
      (fields
        (field (name "MANUFACTURER") "VIKING")
        (field (name "MANUFACTURER PART NUMBER") "CR-03FA7--100R")
      )
      (libsource (lib "LIB-CASCO-DATA-SMD") (part "SMD-R-CR-03FA7--100R"))
    )
    (comp (ref "R27")
      (value "100k")
      (footprint "SMD-R-0603")
      (description "603 AEC-Q200")
      (fields
        (field (name "MANUFACTURER") "VIKING")
        (field (name "MANUFACTURER PART NUMBER") "CR-03FA7--100R")
      )
      (libsource (lib "LIB-CASCO-DATA-SMD") (part "SMD-R-CR-03FA7--100R"))
    )
    (comp (ref "R28")
      (value "8.2k")
      (footprint "SMD-R-0603")
      (description "603 AEC-Q200")
      (fields
        (field (name "MANUFACTURER") "VIKING")
        (field (name "MANUFACTURER PART NUMBER") "CR-03FA7--100R")
      )
      (libsource (lib "LIB-CASCO-DATA-SMD") (part "SMD-R-CR-03FA7--100R"))
    )
    (comp (ref "R29")
      (value "10k")
      (footprint "SMD-R-0603")
      (description "603 AEC-Q200")
      (fields
        (field (name "MANUFACTURER") "VIKING")
        (field (name "MANUFACTURER PART NUMBER") "CR-03FA7--100R")
        (field (name "PACKAGE OR CASE") "0603")
      )
      (libsource (lib "LIB-CASCO-DATA-SMD") (part "SMD-R-CR-03FA7--100R"))
    )
    (comp (ref "R30")
      (value "10k")
      (footprint "SMD-R-0603")
      (description "603 AEC-Q200")
      (fields
        (field (name "MANUFACTURER") "VIKING")
        (field (name "MANUFACTURER PART NUMBER") "CR-03FA7--100R")
      )
      (libsource (lib "LIB-CASCO-DATA-SMD") (part "SMD-R-CR-03FA7--100R"))
    )
    (comp (ref "R31")
      (value "36k")
      (footprint "SMD-R-0603")
      (description "603 AEC-Q200")
      (fields
        (field (name "MANUFACTURER") "VIKING")
        (field (name "MANUFACTURER PART NUMBER") "CR-03FA7--100R")
      )
      (libsource (lib "LIB-CASCO-DATA-SMD") (part "SMD-R-CR-03FA7--100R"))
    )
    (comp (ref "R32")
      (value "10k")
      (footprint "SMD-R-0603")
      (description "603 AEC-Q200")
      (fields
        (field (name "MANUFACTURER") "VIKING")
        (field (name "MANUFACTURER PART NUMBER") "CR-03FA7--100R")
      )
      (libsource (lib "LIB-CASCO-DATA-SMD") (part "SMD-R-CR-03FA7--100R"))
    )
    (comp (ref "R33")
      (value "10k")
      (footprint "SMD-R-0603")
      (description "603 AEC-Q200")
      (fields
        (field (name "MANUFACTURER") "VIKING")
        (field (name "MANUFACTURER PART NUMBER") "CR-03FA7--100R")
      )
      (libsource (lib "LIB-CASCO-DATA-SMD") (part "SMD-R-CR-03FA7--100R"))
    )
    (comp (ref "R34")
      (value "47k")
      (footprint "SMD-R-0603")
      (description "603 AEC-Q200")
      (fields
        (field (name "MANUFACTURER") "VIKING")
        (field (name "MANUFACTURER PART NUMBER") "CR-03FA7--100R")
      )
      (libsource (lib "LIB-CASCO-DATA-SMD") (part "SMD-R-CR-03FA7--100R"))
    )
    (comp (ref "R35")
      (value "1k")
      (footprint "SMD-R-0603")
      (description "603 AEC-Q200")
      (fields
        (field (name "MANUFACTURER") "VIKING")
        (field (name "MANUFACTURER PART NUMBER") "CR-03FA7--100R")
      )
      (libsource (lib "LIB-CASCO-DATA-SMD") (part "SMD-R-CR-03FA7--100R"))
    )
    (comp (ref "R36")
      (value "10k")
      (footprint "SMD-R-0603")
      (description "603 AEC-Q200")
      (fields
        (field (name "MANUFACTURER") "VIKING")
        (field (name "MANUFACTURER PART NUMBER") "CR-03FA7--100R")
      )
      (libsource (lib "LIB-CASCO-DATA-SMD") (part "SMD-R-CR-03FA7--100R"))
    )
    (comp (ref "R37")
      (value "0R")
      (footprint "SMD-R-0603")
      (description "603 AEC-Q200")
      (fields
        (field (name "MANUFACTURER") "VIKING")
        (field (name "MANUFACTURER PART NUMBER") "CR-03FA7--100R")
      )
      (libsource (lib "LIB-CASCO-DATA-SMD") (part "SMD-R-CR-03FA7--100R"))
    )
    (comp (ref "R38")
      (value "0R")
      (footprint "SMD-R-0603")
      (description "603 AEC-Q200")
      (fields
        (field (name "MANUFACTURER") "VIKING")
        (field (name "MANUFACTURER PART NUMBER") "CR-03FA7--100R")
      )
      (libsource (lib "LIB-CASCO-DATA-SMD") (part "SMD-R-CR-03FA7--100R"))
    )
    (comp (ref "R39")
      (value "0R")
      (footprint "SMD-R-0603")
      (description "603 AEC-Q200")
      (fields
        (field (name "MANUFACTURER") "VIKING")
        (field (name "MANUFACTURER PART NUMBER") "CR-03FA7--100R")
      )
      (libsource (lib "LIB-CASCO-DATA-SMD") (part "SMD-R-CR-03FA7--100R"))
    )
    (comp (ref "R40")
      (value "0R")
      (footprint "SMD-R-0603")
      (description "603 AEC-Q200")
      (fields
        (field (name "MANUFACTURER") "VIKING")
        (field (name "MANUFACTURER PART NUMBER") "CR-03FA7--100R")
      )
      (libsource (lib "LIB-CASCO-DATA-SMD") (part "SMD-R-CR-03FA7--100R"))
    )
    (comp (ref "R41")
      (value "0R")
      (footprint "SMD-R-0603")
      (description "603 AEC-Q200")
      (fields
        (field (name "MANUFACTURER") "VIKING")
        (field (name "MANUFACTURER PART NUMBER") "CR-03FA7--100R")
      )
      (libsource (lib "LIB-CASCO-DATA-SMD") (part "SMD-R-CR-03FA7--100R"))
    )
    (comp (ref "R42")
      (value "0R")
      (footprint "SMD-R-0603")
      (description "603 AEC-Q200")
      (fields
        (field (name "MANUFACTURER") "VIKING")
        (field (name "MANUFACTURER PART NUMBER") "CR-03FA7--100R")
      )
      (libsource (lib "LIB-CASCO-DATA-SMD") (part "SMD-R-CR-03FA7--100R"))
    )
    (comp (ref "R43")
      (value "0R")
      (footprint "SMD-R-0603")
      (description "603 AEC-Q200")
      (fields
        (field (name "MANUFACTURER") "VIKING")
        (field (name "MANUFACTURER PART NUMBER") "CR-03FA7--100R")
      )
      (libsource (lib "LIB-CASCO-DATA-SMD") (part "SMD-R-CR-03FA7--100R"))
    )
    (comp (ref "R44")
      (value "0R")
      (footprint "SMD-R-0603")
      (description "603 AEC-Q200")
      (fields
        (field (name "MANUFACTURER") "VIKING")
        (field (name "MANUFACTURER PART NUMBER") "CR-03FA7--100R")
      )
      (libsource (lib "LIB-CASCO-DATA-SMD") (part "SMD-R-CR-03FA7--100R"))
    )
    (comp (ref "R45")
      (value "4.7k")
      (footprint "SMD-R-0603")
      (description "603 AEC-Q200")
      (fields
        (field (name "MANUFACTURER") "VIKING")
        (field (name "MANUFACTURER PART NUMBER") "CR-03FA7--100R")
      )
      (libsource (lib "LIB-CASCO-DATA-SMD") (part "SMD-R-CR-03FA7--100R"))
    )
    (comp (ref "R46")
      (value "4.7k")
      (footprint "SMD-R-0603")
      (description "603 AEC-Q200")
      (fields
        (field (name "MANUFACTURER") "VIKING")
        (field (name "MANUFACTURER PART NUMBER") "CR-03FA7--100R")
      )
      (libsource (lib "LIB-CASCO-DATA-SMD") (part "SMD-R-CR-03FA7--100R"))
    )
    (comp (ref "R47")
      (value "10k")
      (footprint "SMD-R-0603")
      (description "603 AEC-Q200")
      (fields
        (field (name "MANUFACTURER") "VIKING")
        (field (name "MANUFACTURER PART NUMBER") "CR-03FA7--100R")
      )
      (libsource (lib "LIB-CASCO-DATA-SMD") (part "SMD-R-CR-03FA7--100R"))
    )
    (comp (ref "R48")
      (value "4.7k")
      (footprint "SMD-R-0603")
      (description "603 AEC-Q200")
      (fields
        (field (name "MANUFACTURER") "VIKING")
        (field (name "MANUFACTURER PART NUMBER") "CR-03FA7--100R")
      )
      (libsource (lib "LIB-CASCO-DATA-SMD") (part "SMD-R-CR-03FA7--100R"))
    )
    (comp (ref "R49")
      (value "6.8k")
      (footprint "SMD-R-0603")
      (description "603 AEC-Q200")
      (fields
        (field (name "MANUFACTURER") "VIKING")
        (field (name "MANUFACTURER PART NUMBER") "CR-03FA7--100R")
      )
      (libsource (lib "LIB-CASCO-DATA-SMD") (part "SMD-R-CR-03FA7--100R"))
    )
    (comp (ref "R50")
      (value "10k")
      (footprint "SMD-R-0603")
      (description "603 AEC-Q200")
      (fields
        (field (name "MANUFACTURER") "VIKING")
        (field (name "MANUFACTURER PART NUMBER") "CR-03FA7--100R")
      )
      (libsource (lib "LIB-CASCO-DATA-SMD") (part "SMD-R-CR-03FA7--100R"))
    )
    (comp (ref "R51")
      (value "0R")
      (footprint "SMD-R-0603")
      (description "603 AEC-Q200")
      (fields
        (field (name "MANUFACTURER") "VIKING")
        (field (name "MANUFACTURER PART NUMBER") "CR-03FA7--100R")
      )
      (libsource (lib "LIB-CASCO-DATA-SMD") (part "SMD-R-CR-03FA7--100R"))
    )
    (comp (ref "R52")
      (value "47R")
      (footprint "SMD-R-0603")
      (description "603 AEC-Q200")
      (fields
        (field (name "MANUFACTURER") "VIKING")
        (field (name "MANUFACTURER PART NUMBER") "CR-03FA7--100R")
      )
      (libsource (lib "LIB-CASCO-DATA-SMD") (part "SMD-R-CR-03FA7--100R"))
    )
    (comp (ref "R53")
      (value "0R")
      (footprint "SMD-R-0603")
      (description "603 AEC-Q200")
      (fields
        (field (name "MANUFACTURER") "VIKING")
        (field (name "MANUFACTURER PART NUMBER") "CR-03FA7--100R")
      )
      (libsource (lib "LIB-CASCO-DATA-SMD") (part "SMD-R-CR-03FA7--100R"))
    )
    (comp (ref "R54")
      (value "10k")
      (footprint "SMD-R-0603")
      (description "603 AEC-Q200")
      (fields
        (field (name "MANUFACTURER") "VIKING")
        (field (name "MANUFACTURER PART NUMBER") "CR-03FA7--100R")
      )
      (libsource (lib "LIB-CASCO-DATA-SMD") (part "SMD-R-CR-03FA7--100R"))
    )
    (comp (ref "R55")
      (value "10k")
      (footprint "SMD-R-0603")
      (description "603 AEC-Q200")
      (fields
        (field (name "MANUFACTURER") "VIKING")
        (field (name "MANUFACTURER PART NUMBER") "CR-03FA7--100R")
      )
      (libsource (lib "LIB-CASCO-DATA-SMD") (part "SMD-R-CR-03FA7--100R"))
    )
    (comp (ref "R56")
      (value "10k")
      (footprint "SMD-R-0603")
      (description "603 AEC-Q200")
      (fields
        (field (name "MANUFACTURER") "VIKING")
        (field (name "MANUFACTURER PART NUMBER") "CR-03FA7--100R")
      )
      (libsource (lib "LIB-CASCO-DATA-SMD") (part "SMD-R-CR-03FA7--100R"))
    )
    (comp (ref "R57")
      (value "10k")
      (footprint "SMD-R-0603")
      (description "603 AEC-Q200")
      (fields
        (field (name "MANUFACTURER") "VIKING")
        (field (name "MANUFACTURER PART NUMBER") "CR-03FA7--100R")
      )
      (libsource (lib "LIB-CASCO-DATA-SMD") (part "SMD-R-CR-03FA7--100R"))
    )
    (comp (ref "R58")
      (value "0R")
      (footprint "SMD-R-0603")
      (description "603 AEC-Q200")
      (fields
        (field (name "MANUFACTURER") "VIKING")
        (field (name "MANUFACTURER PART NUMBER") "CR-03FA7--100R")
      )
      (libsource (lib "LIB-CASCO-DATA-SMD") (part "SMD-R-CR-03FA7--100R"))
    )
    (comp (ref "R59")
      (value "10k")
      (footprint "SMD-R-0603")
      (description "603 AEC-Q200")
      (fields
        (field (name "MANUFACTURER") "VIKING")
        (field (name "MANUFACTURER PART NUMBER") "CR-03FA7--100R")
      )
      (libsource (lib "LIB-CASCO-DATA-SMD") (part "SMD-R-CR-03FA7--100R"))
    )
    (comp (ref "R60")
      (value "0R")
      (footprint "SMD-R-0603")
      (description "603 AEC-Q200")
      (fields
        (field (name "MANUFACTURER") "VIKING")
        (field (name "MANUFACTURER PART NUMBER") "CR-03FA7--100R")
      )
      (libsource (lib "LIB-CASCO-DATA-SMD") (part "SMD-R-CR-03FA7--100R"))
    )
    (comp (ref "R61")
      (value "0R")
      (footprint "SMD-R-0603")
      (description "603 AEC-Q200")
      (fields
        (field (name "MANUFACTURER") "VIKING")
        (field (name "MANUFACTURER PART NUMBER") "CR-03FA7--100R")
      )
      (libsource (lib "LIB-CASCO-DATA-SMD") (part "SMD-R-CR-03FA7--100R"))
    )
    (comp (ref "R62")
      (value "10k")
      (footprint "SMD-R-0603")
      (description "603 AEC-Q200")
      (fields
        (field (name "MANUFACTURER") "VIKING")
        (field (name "MANUFACTURER PART NUMBER") "CR-03FA7--100R")
      )
      (libsource (lib "LIB-CASCO-DATA-SMD") (part "SMD-R-CR-03FA7--100R"))
    )
    (comp (ref "R63")
      (value "0R")
      (footprint "SMD-R-0603")
      (description "603 AEC-Q200")
      (fields
        (field (name "MANUFACTURER") "VIKING")
        (field (name "MANUFACTURER PART NUMBER") "CR-03FA7--100R")
      )
      (libsource (lib "LIB-CASCO-DATA-SMD") (part "SMD-R-CR-03FA7--100R"))
    )
    (comp (ref "R64")
      (value "0R")
      (footprint "SMD-R-0603")
      (description "603 AEC-Q200")
      (fields
        (field (name "MANUFACTURER") "VIKING")
        (field (name "MANUFACTURER PART NUMBER") "CR-03FA7--100R")
      )
      (libsource (lib "LIB-CASCO-DATA-SMD") (part "SMD-R-CR-03FA7--100R"))
    )
    (comp (ref "R65")
      (value "0R")
      (footprint "SMD-R-0603")
      (description "603 AEC-Q200")
      (fields
        (field (name "MANUFACTURER") "VIKING")
        (field (name "MANUFACTURER PART NUMBER") "CR-03FA7--100R")
      )
      (libsource (lib "LIB-CASCO-DATA-SMD") (part "SMD-R-CR-03FA7--100R"))
    )
    (comp (ref "R66")
      (value "0R")
      (footprint "SMD-R-0603")
      (description "603 AEC-Q200")
      (fields
        (field (name "MANUFACTURER") "VIKING")
        (field (name "MANUFACTURER PART NUMBER") "CR-03FA7--100R")
      )
      (libsource (lib "LIB-CASCO-DATA-SMD") (part "SMD-R-CR-03FA7--100R"))
    )
    (comp (ref "R67")
      (value "0R")
      (footprint "SMD-R-0603")
      (description "603 AEC-Q200")
      (fields
        (field (name "MANUFACTURER") "VIKING")
        (field (name "MANUFACTURER PART NUMBER") "CR-03FA7--100R")
      )
      (libsource (lib "LIB-CASCO-DATA-SMD") (part "SMD-R-CR-03FA7--100R"))
    )
    (comp (ref "R68")
      (value "0R")
      (footprint "SMD-R-0603")
      (description "603 AEC-Q200")
      (fields
        (field (name "MANUFACTURER") "VIKING")
        (field (name "MANUFACTURER PART NUMBER") "CR-03FA7--100R")
      )
      (libsource (lib "LIB-CASCO-DATA-SMD") (part "SMD-R-CR-03FA7--100R"))
    )
    (comp (ref "R69")
      (value "0R")
      (footprint "SMD-R-0603")
      (description "603 AEC-Q200")
      (fields
        (field (name "MANUFACTURER") "VIKING")
        (field (name "MANUFACTURER PART NUMBER") "CR-03FA7--100R")
      )
      (libsource (lib "LIB-CASCO-DATA-SMD") (part "SMD-R-CR-03FA7--100R"))
    )
    (comp (ref "R70")
      (value "6.8k")
      (footprint "SMD-R-0603")
      (description "603 AEC-Q200")
      (fields
        (field (name "MANUFACTURER") "VIKING")
        (field (name "MANUFACTURER PART NUMBER") "CR-03FA7--100R")
      )
      (libsource (lib "LIB-CASCO-DATA-SMD") (part "SMD-R-CR-03FA7--100R"))
    )
    (comp (ref "R71")
      (value "10k")
      (footprint "SMD-R-0603")
      (description "603 AEC-Q200")
      (fields
        (field (name "MANUFACTURER") "VIKING")
        (field (name "MANUFACTURER PART NUMBER") "CR-03FA7--100R")
      )
      (libsource (lib "LIB-CASCO-DATA-SMD") (part "SMD-R-CR-03FA7--100R"))
    )
    (comp (ref "R72")
      (value "6.8k")
      (footprint "SMD-R-0603")
      (description "603 AEC-Q200")
      (fields
        (field (name "MANUFACTURER") "VIKING")
        (field (name "MANUFACTURER PART NUMBER") "CR-03FA7--100R")
      )
      (libsource (lib "LIB-CASCO-DATA-SMD") (part "SMD-R-CR-03FA7--100R"))
    )
    (comp (ref "R73")
      (value "10k")
      (footprint "SMD-R-0603")
      (description "603 AEC-Q200")
      (fields
        (field (name "MANUFACTURER") "VIKING")
        (field (name "MANUFACTURER PART NUMBER") "CR-03FA7--100R")
      )
      (libsource (lib "LIB-CASCO-DATA-SMD") (part "SMD-R-CR-03FA7--100R"))
    )
    (comp (ref "R74")
      (value "47R")
      (footprint "SMD-R-0603")
      (description "603 AEC-Q200")
      (fields
        (field (name "MANUFACTURER") "VIKING")
        (field (name "MANUFACTURER PART NUMBER") "CR-03FA7--100R")
      )
      (libsource (lib "LIB-CASCO-DATA-SMD") (part "SMD-R-CR-03FA7--100R"))
    )
    (comp (ref "R75")
      (value "47R")
      (footprint "SMD-R-0603")
      (description "603 AEC-Q200")
      (fields
        (field (name "MANUFACTURER") "VIKING")
        (field (name "MANUFACTURER PART NUMBER") "CR-03FA7--100R")
      )
      (libsource (lib "LIB-CASCO-DATA-SMD") (part "SMD-R-CR-03FA7--100R"))
    )
    (comp (ref "S1")
      (value "SW-PB")
      (footprint "SMD-SW-2")
      (description "Switch")
      (fields (field (name "PUBLISHER") "Altium Limited"))
      (libsource (lib "Miscellaneous Devices") (part "SW-PB"))
    )
    (comp (ref "S2")
      (value "SW-PB")
      (footprint "SMD-SW-2")
      (description "Switch")
      (fields (field (name "PUBLISHER") "Altium Limited"))
      (libsource (lib "Miscellaneous Devices") (part "SW-PB"))
    )
    (comp (ref "S3")
      (value "SW-PB")
      (footprint "SMD-SW-2")
      (description "Switch")
      (fields (field (name "PUBLISHER") "Altium Limited"))
      (libsource (lib "Miscellaneous Devices") (part "SW-PB"))
    )
    (comp (ref "S4")
      (value "SW-PB")
      (footprint "SMD-SW-2")
      (description "Switch")
      (fields (field (name "PUBLISHER") "Altium Limited"))
      (libsource (lib "Miscellaneous Devices") (part "SW-PB"))
    )
    (comp (ref "U1") (value "LM78M05CDT") (footprint "TO-252") (libsource (lib "Schlib1") (part "LM78M05")))
    (comp (ref "U2")
      (value "USBLC6-2P6")
      (footprint "SOT-666")
      (libsource (lib "Schlib1") (part "USBLC6-2P6"))
    )
    (comp (ref "U3") (value "SY8253ADC") (footprint "SOT23-6") (libsource (lib "Schlib1") (part "SY8253ADC")))
    (comp (ref "U4")
      (value "SCJT1117B-3.3")
      (footprint "SMD-SOT223")
      (libsource (lib "Schlib1") (part "SCJT1117B-3.3"))
    )
    (comp (ref "U5") (value "TMP117AIDRVR") (footprint "TMP117") (libsource (lib "Schlib1") (part "TMP117")))
    (comp (ref "U6")
      (value "STM32F401RC")
      (footprint "STM32F401RCT6")
      (libsource (lib "Schlib1") (part "STM32F401RC"))
    )
    (comp (ref "U7")
      (value "ADS1113IDGSR")
      (footprint "VSSOP-10")
      (libsource (lib "Schlib1") (part "ADS1113"))
    )
    (comp (ref "Y1")
      (value "ABM8-16.000MHZ-B2-T")
      (footprint "ABM8")
      (libsource (lib "Schlib1") (part "Crystal"))
    )
  )
  (nets
    (net (code "1") (name "+3.3V") (class "Default")
      (node (ref "C17") (pin "1") (pinfunction "1_1") (pintype "passive"))
      (node (ref "C19") (pin "1") (pinfunction "1_1") (pintype "passive"))
      (node (ref "C21") (pin "1") (pinfunction "1_1") (pintype "passive"))
      (node (ref "C23") (pin "1") (pinfunction "1_1") (pintype "passive"))
      (node (ref "C25") (pin "1") (pinfunction "1_1") (pintype "passive"))
      (node (ref "C26") (pin "1") (pinfunction "1_1") (pintype "passive"))
      (node (ref "C27") (pin "1") (pinfunction "1_1") (pintype "passive"))
      (node (ref "C31") (pin "2") (pinfunction "2_2") (pintype "passive"))
      (node (ref "C35") (pin "2") (pinfunction "2_2") (pintype "passive"))
      (node (ref "C36") (pin "2") (pinfunction "2_2") (pintype "passive"))
      (node (ref "C37") (pin "2") (pinfunction "2_2") (pintype "passive"))
      (node (ref "C38") (pin "1") (pinfunction "1_1") (pintype "passive"))
      (node (ref "C39") (pin "1") (pinfunction "1_1") (pintype "passive"))
      (node (ref "C40") (pin "1") (pinfunction "1_1") (pintype "passive"))
      (node (ref "C41") (pin "1") (pinfunction "1_1") (pintype "passive"))
      (node (ref "C42") (pin "1") (pinfunction "1_1") (pintype "passive"))
      (node (ref "C44") (pin "1") (pinfunction "1_1") (pintype "passive"))
      (node (ref "C45") (pin "1") (pinfunction "1_1") (pintype "passive"))
      (node (ref "C51") (pin "1") (pinfunction "1_1") (pintype "passive"))
      (node (ref "J12") (pin "4") (pinfunction "4_4") (pintype "passive"))
      (node (ref "J15") (pin "4") (pinfunction "4_4") (pintype "passive"))
      (node (ref "J18") (pin "4") (pinfunction "4_4") (pintype "passive"))
      (node (ref "J6") (pin "2") (pinfunction "2_2") (pintype "passive"))
      (node (ref "J7") (pin "1") (pinfunction "1_1") (pintype "passive"))
      (node (ref "J7") (pin "13") (pinfunction "13_13") (pintype "passive"))
      (node (ref "J8") (pin "2") (pinfunction "2_2") (pintype "passive"))
      (node (ref "J9") (pin "2") (pinfunction "2_2") (pintype "passive"))
      (node (ref "Q1") (pin "6") (pinfunction "6_6") (pintype "passive"))
      (node (ref "R34") (pin "1") (pinfunction "1_1") (pintype "passive"))
      (node (ref "R36") (pin "1") (pinfunction "1_1") (pintype "passive"))
      (node (ref "R41") (pin "2") (pinfunction "2_2") (pintype "passive"))
      (node (ref "R44") (pin "2") (pinfunction "2_2") (pintype "passive"))
      (node (ref "R45") (pin "1") (pinfunction "1_1") (pintype "passive"))
      (node (ref "R46") (pin "1") (pinfunction "1_1") (pintype "passive"))
      (node (ref "R48") (pin "1") (pinfunction "1_1") (pintype "passive"))
      (node (ref "R54") (pin "2") (pinfunction "2_2") (pintype "passive"))
      (node (ref "R55") (pin "2") (pinfunction "2_2") (pintype "passive"))
      (node (ref "R56") (pin "1") (pinfunction "1_1") (pintype "passive"))
      (node (ref "R57") (pin "1") (pinfunction "1_1") (pintype "passive"))
      (node (ref "R59") (pin "1") (pinfunction "1_1") (pintype "passive"))
      (node (ref "R61") (pin "2") (pinfunction "2_2") (pintype "passive"))
      (node (ref "R62") (pin "1") (pinfunction "1_1") (pintype "passive"))
      (node (ref "R65") (pin "2") (pinfunction "2_2") (pintype "passive"))
      (node (ref "R66") (pin "2") (pinfunction "2_2") (pintype "passive"))
      (node (ref "R69") (pin "2") (pinfunction "2_2") (pintype "passive"))
      (node (ref "S1") (pin "2") (pinfunction "2_2") (pintype "passive"))
      (node (ref "S2") (pin "2") (pinfunction "2_2") (pintype "passive"))
      (node (ref "S3") (pin "2") (pinfunction "2_2") (pintype "passive"))
      (node (ref "U4") (pin "2") (pinfunction "VO_2") (pintype "passive"))
      (node (ref "U5") (pin "5") (pinfunction "V+_5") (pintype "power_in"))
      (node (ref "U6") (pin "1") (pinfunction "VBAT_1") (pintype "power_in"))
      (node (ref "U6") (pin "13") (pinfunction "VDDA_13") (pintype "power_in"))
      (node (ref "U6") (pin "19") (pinfunction "VDD_4_19") (pintype "power_in"))
      (node (ref "U6") (pin "32") (pinfunction "VDD_1_32") (pintype "power_in"))
      (node (ref "U6") (pin "48") (pinfunction "VDD_2_48") (pintype "power_in"))
      (node (ref "U6") (pin "64") (pinfunction "VDD_3_64") (pintype "power_in"))
      (node (ref "U7") (pin "8") (pinfunction "VDD_8") (pintype "power_in"))
    )
    (net (code "2") (name "+5V") (class "Default")
      (node (ref "C11") (pin "1") (pinfunction "1_1") (pintype "passive"))
      (node (ref "C12") (pin "1") (pinfunction "1_1") (pintype "passive"))
      (node (ref "C48") (pin "2") (pinfunction "2_2") (pintype "passive"))
      (node (ref "D3") (pin "1") (pinfunction "A_1") (pintype "passive"))
      (node (ref "J4") (pin "2") (pinfunction "Sen_2") (pintype "passive"))
      (node (ref "J6") (pin "1") (pinfunction "1_1") (pintype "passive"))
      (node (ref "J7") (pin "23") (pinfunction "23_23") (pintype "passive"))
      (node (ref "R37") (pin "2") (pinfunction "2_2") (pintype "passive"))
      (node (ref "R39") (pin "2") (pinfunction "2_2") (pintype "passive"))
      (node (ref "R58") (pin "2") (pinfunction "2_2") (pintype "passive"))
      (node (ref "R63") (pin "2") (pinfunction "2_2") (pintype "passive"))
      (node (ref "R70") (pin "1") (pinfunction "1_1") (pintype "passive"))
      (node (ref "U4") (pin "3") (pinfunction "IN_3") (pintype "passive"))
    )
    (net (code "3") (name "+5V_Supply") (class "Default")
      (node (ref "C9") (pin "1") (pinfunction "1_1") (pintype "passive"))
      (node (ref "J4") (pin "3") (pinfunction "V2_3") (pintype "passive"))
      (node (ref "U1") (pin "2") (pinfunction "VO_2") (pintype "passive"))
    )
    (net (code "4") (name "/ARM_ADC_AN0") (class "Default")
      (node (ref "C50") (pin "2") (pinfunction "2_2") (pintype "passive"))
      (node (ref "R75") (pin "2") (pinfunction "2_2") (pintype "passive"))
      (node (ref "U6") (pin "14") (pinfunction "PA0_14") (pintype "bidirectional"))
    )
    (net (code "5") (name "/ARM_ADC_AN1") (class "Default")
      (node (ref "R10") (pin "2") (pinfunction "2_2") (pintype "passive"))
      (node (ref "U6") (pin "15") (pinfunction "PA1_15") (pintype "bidirectional"))
    )
    (net (code "6") (name "/ARM_ADC_AN2") (class "Default")
      (node (ref "C49") (pin "2") (pinfunction "2_2") (pintype "passive"))
      (node (ref "R74") (pin "2") (pinfunction "2_2") (pintype "passive"))
      (node (ref "U6") (pin "16") (pinfunction "PA2_16") (pintype "bidirectional"))
    )
    (net (code "7") (name "/ARM_ADC_AN3") (class "Default")
      (node (ref "C14") (pin "1") (pinfunction "1_1") (pintype "passive"))
      (node (ref "R15") (pin "2") (pinfunction "2_2") (pintype "passive"))
      (node (ref "U6") (pin "17") (pinfunction "PA3_17") (pintype "bidirectional"))
    )
    (net (code "8") (name "/ARM_ADS_SCL") (class "Default")
      (node (ref "R54") (pin "1") (pinfunction "1_1") (pintype "passive"))
      (node (ref "U6") (pin "56") (pinfunction "PB4_56") (pintype "bidirectional"))
      (node (ref "U7") (pin "10") (pinfunction "SCL_10") (pintype "passive"))
    )
    (net (code "9") (name "/ARM_ADS_SDA") (class "Default")
      (node (ref "R55") (pin "1") (pinfunction "1_1") (pintype "passive"))
      (node (ref "U6") (pin "57") (pinfunction "PB5_57") (pintype "bidirectional"))
      (node (ref "U7") (pin "9") (pinfunction "SDA_9") (pintype "passive"))
    )
    (net (code "10") (name "/ARM_I2C3_SCL") (class "Default")
      (node (ref "J17") (pin "1") (pinfunction "1_1") (pintype "passive"))
      (node (ref "R57") (pin "2") (pinfunction "2_2") (pintype "passive"))
      (node (ref "U6") (pin "41") (pinfunction "PA8_41") (pintype "bidirectional"))
    )
    (net (code "11") (name "/ARM_I2C3_SDA") (class "Default")
      (node (ref "J17") (pin "2") (pinfunction "2_2") (pintype "passive"))
      (node (ref "R56") (pin "2") (pinfunction "2_2") (pintype "passive"))
      (node (ref "U6") (pin "40") (pinfunction "PC9_40") (pintype "bidirectional"))
    )
    (net (code "12") (name "/ARM_KEY1") (class "Default")
      (node (ref "R30") (pin "1") (pinfunction "1_1") (pintype "passive"))
      (node (ref "S1") (pin "1") (pinfunction "1_1") (pintype "passive"))
      (node (ref "U6") (pin "8") (pinfunction "PC0_8") (pintype "bidirectional"))
    )
    (net (code "13") (name "/ARM_KEY2") (class "Default")
      (node (ref "R32") (pin "1") (pinfunction "1_1") (pintype "passive"))
      (node (ref "S2") (pin "1") (pinfunction "1_1") (pintype "passive"))
      (node (ref "U6") (pin "9") (pinfunction "PC1_9") (pintype "bidirectional"))
    )
    (net (code "14") (name "/ARM_KEY3") (class "Default")
      (node (ref "R33") (pin "1") (pinfunction "1_1") (pintype "passive"))
      (node (ref "S3") (pin "1") (pinfunction "1_1") (pintype "passive"))
      (node (ref "U6") (pin "10") (pinfunction "PC2_10") (pintype "bidirectional"))
    )
    (net (code "15") (name "/ARM_LCD_SCL") (class "Default")
      (node (ref "J8") (pin "3") (pinfunction "3_3") (pintype "passive"))
      (node (ref "U6") (pin "61") (pinfunction "PB8_61") (pintype "bidirectional"))
    )
    (net (code "16") (name "/ARM_LCD_SDA") (class "Default")
      (node (ref "J8") (pin "4") (pinfunction "4_4") (pintype "passive"))
      (node (ref "U6") (pin "62") (pinfunction "PB9_62") (pintype "bidirectional"))
    )
    (net (code "17") (name "/ARM_LED") (class "Default")
      (node (ref "D5") (pin "1") (pinfunction "A_1") (pintype "passive"))
      (node (ref "U6") (pin "11") (pinfunction "PC3_11") (pintype "bidirectional"))
    )
    (net (code "18") (name "/ARM_PA4") (class "Default")
      (node (ref "R16") (pin "2") (pinfunction "2_2") (pintype "passive"))
      (node (ref "U6") (pin "20") (pinfunction "PA4_20") (pintype "bidirectional"))
    )
    (net (code "19") (name "/ARM_PA15") (class "Default")
      (node (ref "R35") (pin "2") (pinfunction "2_2") (pintype "passive"))
      (node (ref "U6") (pin "50") (pinfunction "PA15_50") (pintype "bidirectional"))
    )
    (net (code "20") (name "/ARM_PB0") (class "Default")
      (node (ref "R23") (pin "2") (pinfunction "2_2") (pintype "passive"))
      (node (ref "U6") (pin "26") (pinfunction "PB0_26") (pintype "bidirectional"))
    )
    (net (code "21") (name "/ARM_PB1") (class "Default")
      (node (ref "R7") (pin "2") (pinfunction "2_2") (pintype "passive"))
      (node (ref "U6") (pin "27") (pinfunction "PB1_27") (pintype "bidirectional"))
    )
    (net (code "22") (name "/ARM_PB2") (class "Default")
      (node (ref "R6") (pin "2") (pinfunction "2_2") (pintype "passive"))
      (node (ref "U6") (pin "28") (pinfunction "PB2_28") (pintype "bidirectional"))
    )
    (net (code "23") (name "/ARM_PB12") (class "Default")
      (node (ref "R5") (pin "2") (pinfunction "2_2") (pintype "passive"))
      (node (ref "U6") (pin "33") (pinfunction "PB12_33") (pintype "bidirectional"))
    )
    (net (code "24") (name "/ARM_PB13") (class "Default")
      (node (ref "R4") (pin "2") (pinfunction "2_2") (pintype "passive"))
      (node (ref "U6") (pin "34") (pinfunction "PB13_34") (pintype "bidirectional"))
    )
    (net (code "25") (name "/ARM_PB14") (class "Default")
      (node (ref "R3") (pin "2") (pinfunction "2_2") (pintype "passive"))
      (node (ref "U6") (pin "35") (pinfunction "PB14_35") (pintype "bidirectional"))
    )
    (net (code "26") (name "/ARM_PB15") (class "Default")
      (node (ref "R2") (pin "2") (pinfunction "2_2") (pintype "passive"))
      (node (ref "U6") (pin "36") (pinfunction "PB15_36") (pintype "bidirectional"))
    )
    (net (code "27") (name "/ARM_PC4") (class "Default")
      (node (ref "R20") (pin "2") (pinfunction "2_2") (pintype "passive"))
      (node (ref "U6") (pin "24") (pinfunction "PC4_24") (pintype "bidirectional"))
    )
    (net (code "28") (name "/ARM_PC5") (class "Default")
      (node (ref "R21") (pin "2") (pinfunction "2_2") (pintype "passive"))
      (node (ref "U6") (pin "25") (pinfunction "PC5_25") (pintype "bidirectional"))
    )
    (net (code "29") (name "/ARM_PC8") (class "Default")
      (node (ref "R22") (pin "2") (pinfunction "2_2") (pintype "passive"))
      (node (ref "U6") (pin "39") (pinfunction "PC8_39") (pintype "bidirectional"))
    )
    (net (code "30") (name "/ARM_PC14") (class "Default")
      (node (ref "R18") (pin "2") (pinfunction "2_2") (pintype "passive"))
      (node (ref "U6") (pin "3") (pinfunction "PC14-OSC32_IN_3") (pintype "bidirectional"))
    )
    (net (code "31") (name "/ARM_PC15") (class "Default")
      (node (ref "R19") (pin "2") (pinfunction "2_2") (pintype "passive"))
      (node (ref "U6") (pin "4") (pinfunction "PC15-OSC32_OUT_4") (pintype "bidirectional"))
    )
    (net (code "32") (name "/ARM_PD2") (class "Default")
      (node (ref "R17") (pin "2") (pinfunction "2_2") (pintype "passive"))
      (node (ref "U6") (pin "54") (pinfunction "PD2_54") (pintype "bidirectional"))
    )
    (net (code "33") (name "/ARM_SENS_I2C_SCL") (class "Default")
      (node (ref "J16") (pin "1") (pinfunction "1_1") (pintype "passive"))
      (node (ref "R62") (pin "2") (pinfunction "2_2") (pintype "passive"))
      (node (ref "U6") (pin "58") (pinfunction "PB6_58") (pintype "bidirectional"))
    )
    (net (code "34") (name "/ARM_SENS_I2C_SDA") (class "Default")
      (node (ref "J16") (pin "2") (pinfunction "2_2") (pintype "passive"))
      (node (ref "R59") (pin "2") (pinfunction "2_2") (pintype "passive"))
      (node (ref "U6") (pin "59") (pinfunction "PB7_59") (pintype "bidirectional"))
    )
    (net (code "35") (name "/ARM_SPI1_MISO") (class "Default")
      (node (ref "J15") (pin "2") (pinfunction "2_2") (pintype "passive"))
      (node (ref "U6") (pin "22") (pinfunction "PA6_22") (pintype "bidirectional"))
    )
    (net (code "36") (name "/ARM_SPI1_MOSI") (class "Default")
      (node (ref "J15") (pin "3") (pinfunction "3_3") (pintype "passive"))
      (node (ref "U6") (pin "23") (pinfunction "PA7_23") (pintype "bidirectional"))
    )
    (net (code "37") (name "/ARM_SPI1_SCK") (class "Default")
      (node (ref "J15") (pin "1") (pinfunction "1_1") (pintype "passive"))
      (node (ref "U6") (pin "21") (pinfunction "PA5_21") (pintype "bidirectional"))
    )
    (net (code "38") (name "/ARM_SPI3_MISO") (class "Default")
      (node (ref "J18") (pin "2") (pinfunction "2_2") (pintype "passive"))
      (node (ref "U6") (pin "52") (pinfunction "PC11_52") (pintype "bidirectional"))
    )
    (net (code "39") (name "/ARM_SPI3_MOSI") (class "Default")
      (node (ref "J18") (pin "3") (pinfunction "3_3") (pintype "passive"))
      (node (ref "U6") (pin "53") (pinfunction "PC12_53") (pintype "bidirectional"))
    )
    (net (code "40") (name "/ARM_SPI3_SCK") (class "Default")
      (node (ref "J18") (pin "1") (pinfunction "1_1") (pintype "passive"))
      (node (ref "U6") (pin "51") (pinfunction "PC10_51") (pintype "bidirectional"))
    )
    (net (code "41") (name "/ARM_UART1_RX") (class "Default")
      (node (ref "R9") (pin "2") (pinfunction "2_2") (pintype "passive"))
      (node (ref "U6") (pin "43") (pinfunction "PA10_43") (pintype "bidirectional"))
    )
    (net (code "42") (name "/ARM_UART1_TX") (class "Default")
      (node (ref "R8") (pin "2") (pinfunction "2_2") (pintype "passive"))
      (node (ref "U6") (pin "42") (pinfunction "PA9_42") (pintype "bidirectional"))
    )
    (net (code "43") (name "/ARM_UART6_RX") (class "Default")
      (node (ref "J6") (pin "4") (pinfunction "4_4") (pintype "passive"))
      (node (ref "U6") (pin "38") (pinfunction "PC7_38") (pintype "bidirectional"))
    )
    (net (code "44") (name "/ARM_UART6_TX") (class "Default")
      (node (ref "J6") (pin "3") (pinfunction "3_3") (pintype "passive"))
      (node (ref "U6") (pin "37") (pinfunction "PC6_37") (pintype "bidirectional"))
    )
    (net (code "45") (name "/ARM_USB_N") (class "Default")
      (node (ref "R13") (pin "2") (pinfunction "2_2") (pintype "passive"))
      (node (ref "U6") (pin "44") (pinfunction "PA11_44") (pintype "bidirectional"))
    )
    (net (code "46") (name "/ARM_USB_P") (class "Default")
      (node (ref "R14") (pin "2") (pinfunction "2_2") (pintype "passive"))
      (node (ref "R24") (pin "1") (pinfunction "1_1") (pintype "passive"))
      (node (ref "U6") (pin "45") (pinfunction "PA12_45") (pintype "bidirectional"))
    )
    (net (code "47") (name "/D_N") (class "Default")
      (node (ref "J3") (pin "2") (pinfunction "2_2") (pintype "passive"))
      (node (ref "J5") (pin "2") (pinfunction "2_2") (pintype "passive"))
      (node (ref "U2") (pin "1") (pinfunction "I/O1_1") (pintype "passive"))
    )
    (net (code "48") (name "/D_P") (class "Default")
      (node (ref "J3") (pin "3") (pinfunction "3_3") (pintype "passive"))
      (node (ref "J5") (pin "3") (pinfunction "3_3") (pintype "passive"))
      (node (ref "U2") (pin "3") (pinfunction "I/O2_3") (pintype "passive"))
    )
    (net (code "49") (name "/I2C2_SCL") (class "Default")
      (node (ref "J9") (pin "4") (pinfunction "4_4") (pintype "passive"))
      (node (ref "R46") (pin "2") (pinfunction "2_2") (pintype "passive"))
      (node (ref "U5") (pin "1") (pinfunction "SCL_1") (pintype "open_collector"))
      (node (ref "U6") (pin "29") (pinfunction "PB10_29") (pintype "bidirectional"))
    )
    (net (code "50") (name "/I2C2_SDA") (class "Default")
      (node (ref "J9") (pin "3") (pinfunction "3_3") (pintype "passive"))
      (node (ref "R48") (pin "2") (pinfunction "2_2") (pintype "passive"))
      (node (ref "U5") (pin "6") (pinfunction "SDA_6") (pintype "bidirectional"))
      (node (ref "U6") (pin "55") (pinfunction "PB3_55") (pintype "bidirectional"))
    )
    (net (code "51") (name "/OSC_IN") (class "Default")
      (node (ref "R43") (pin "2") (pinfunction "2_2") (pintype "passive"))
      (node (ref "U6") (pin "5") (pinfunction "OSC_IN_5") (pintype "input"))
    )
    (net (code "52") (name "/OSC_OUT") (class "Default")
      (node (ref "R42") (pin "2") (pinfunction "2_2") (pintype "passive"))
      (node (ref "U6") (pin "6") (pinfunction "OSC_OUT_6") (pintype "output"))
    )
    (net (code "53") (name "/Power") (class "Default")
      (node (ref "D1") (pin "2") (pinfunction "P+_2") (pintype "passive"))
      (node (ref "J1") (pin "1") (pinfunction "VCC_1") (pintype "passive"))
    )
    (net (code "54") (name "/SWCLK") (class "Default")
      (node (ref "J12") (pin "2") (pinfunction "2_2") (pintype "passive"))
      (node (ref "U6") (pin "49") (pinfunction "PA14/JTCK/SWCLK_49") (pintype "bidirectional"))
    )
    (net (code "55") (name "/SWDIO") (class "Default")
      (node (ref "J12") (pin "3") (pinfunction "3_3") (pintype "passive"))
      (node (ref "U6") (pin "46") (pinfunction "PA13/JTMS/SWDIO_46") (pintype "bidirectional"))
    )
    (net (code "56") (name "/TEMP_ALERT") (class "Default")
      (node (ref "J9") (pin "5") (pinfunction "5_5") (pintype "passive"))
      (node (ref "R45") (pin "2") (pinfunction "2_2") (pintype "passive"))
      (node (ref "U5") (pin "3") (pinfunction "ALERT_3") (pintype "open_collector"))
      (node (ref "U6") (pin "2") (pinfunction "PC13_2") (pintype "bidirectional"))
    )
    (net (code "57") (name "5V") (class "Default")
      (node (ref "C20") (pin "1") (pinfunction "1_1") (pintype "passive"))
      (node (ref "C24") (pin "1") (pinfunction "1_1") (pintype "passive"))
    )
    (net (code "58") (name "8V") (class "Default")
      (node (ref "C15") (pin "1") (pinfunction "1_1") (pintype "passive"))
      (node (ref "C16") (pin "1") (pinfunction "1_1") (pintype "passive"))
      (node (ref "C18") (pin "1") (pinfunction "1_1") (pintype "passive"))
      (node (ref "C22") (pin "1") (pinfunction "1_1") (pintype "passive"))
      (node (ref "J2") (pin "1") (pinfunction "V1_1") (pintype "passive"))
      (node (ref "L1") (pin "2") (pinfunction "2_2") (pintype "passive"))
      (node (ref "R27") (pin "1") (pinfunction "1_1") (pintype "passive"))
    )
    (net (code "59") (name "GND") (class "Default")
      (node (ref "C1") (pin "2") (pinfunction "2_2") (pintype "passive"))
      (node (ref "C10") (pin "1") (pinfunction "1_1") (pintype "passive"))
      (node (ref "C11") (pin "2") (pinfunction "2_2") (pintype "passive"))
      (node (ref "C12") (pin "2") (pinfunction "2_2") (pintype "passive"))
      (node (ref "C14") (pin "2") (pinfunction "2_2") (pintype "passive"))
      (node (ref "C16") (pin "2") (pinfunction "2_2") (pintype "passive"))
      (node (ref "C17") (pin "2") (pinfunction "2_2") (pintype "passive"))
      (node (ref "C18") (pin "2") (pinfunction "2_2") (pintype "passive"))
      (node (ref "C19") (pin "2") (pinfunction "2_2") (pintype "passive"))
      (node (ref "C2") (pin "2") (pinfunction "2_2") (pintype "passive"))
      (node (ref "C20") (pin "2") (pinfunction "2_2") (pintype "passive"))
      (node (ref "C21") (pin "2") (pinfunction "2_2") (pintype "passive"))
      (node (ref "C22") (pin "2") (pinfunction "2_2") (pintype "passive"))
      (node (ref "C23") (pin "2") (pinfunction "2_2") (pintype "passive"))
      (node (ref "C24") (pin "2") (pinfunction "2_2") (pintype "passive"))
      (node (ref "C25") (pin "2") (pinfunction "2_2") (pintype "passive"))
      (node (ref "C26") (pin "2") (pinfunction "2_2") (pintype "passive"))
      (node (ref "C27") (pin "2") (pinfunction "2_2") (pintype "passive"))
      (node (ref "C28") (pin "1") (pinfunction "1_1") (pintype "passive"))
      (node (ref "C29") (pin "2") (pinfunction "2_2") (pintype "passive"))
      (node (ref "C3") (pin "2") (pinfunction "2_2") (pintype "passive"))
      (node (ref "C30") (pin "1") (pinfunction "1_1") (pintype "passive"))
      (node (ref "C31") (pin "1") (pinfunction "1_1") (pintype "passive"))
      (node (ref "C32") (pin "2") (pinfunction "2_2") (pintype "passive"))
      (node (ref "C33") (pin "1") (pinfunction "1_1") (pintype "passive"))
      (node (ref "C34") (pin "1") (pinfunction "1_1") (pintype "passive"))
      (node (ref "C35") (pin "1") (pinfunction "1_1") (pintype "passive"))
      (node (ref "C36") (pin "1") (pinfunction "1_1") (pintype "passive"))
      (node (ref "C37") (pin "1") (pinfunction "1_1") (pintype "passive"))
      (node (ref "C38") (pin "2") (pinfunction "2_2") (pintype "passive"))
      (node (ref "C39") (pin "2") (pinfunction "2_2") (pintype "passive"))
      (node (ref "C4") (pin "2") (pinfunction "2_2") (pintype "passive"))
      (node (ref "C40") (pin "2") (pinfunction "2_2") (pintype "passive"))
      (node (ref "C41") (pin "2") (pinfunction "2_2") (pintype "passive"))
      (node (ref "C42") (pin "2") (pinfunction "2_2") (pintype "passive"))
      (node (ref "C43") (pin "1") (pinfunction "1_1") (pintype "passive"))
      (node (ref "C44") (pin "2") (pinfunction "2_2") (pintype "passive"))
      (node (ref "C45") (pin "2") (pinfunction "2_2") (pintype "passive"))
      (node (ref "C46") (pin "1") (pinfunction "1_1") (pintype "passive"))
      (node (ref "C47") (pin "1") (pinfunction "1_1") (pintype "passive"))
      (node (ref "C48") (pin "1") (pinfunction "1_1") (pintype "passive"))
      (node (ref "C49") (pin "1") (pinfunction "1_1") (pintype "passive"))
      (node (ref "C5") (pin "2") (pinfunction "2_2") (pintype "passive"))
      (node (ref "C50") (pin "1") (pinfunction "1_1") (pintype "passive"))
      (node (ref "C51") (pin "2") (pinfunction "2_2") (pintype "passive"))
      (node (ref "C6") (pin "2") (pinfunction "2_2") (pintype "passive"))
      (node (ref "C7") (pin "2") (pinfunction "2_2") (pintype "passive"))
      (node (ref "C8") (pin "2") (pinfunction "2_2") (pintype "passive"))
      (node (ref "C9") (pin "2") (pinfunction "2_2") (pintype "passive"))
      (node (ref "J1") (pin "2") (pinfunction "GND_2") (pintype "passive"))
      (node (ref "J10") (pin "3") (pinfunction "3_3") (pintype "passive"))
      (node (ref "J11") (pin "6") (pinfunction "GND_6") (pintype "passive"))
      (node (ref "J11") (pin "8") (pinfunction "GND_8") (pintype "passive"))
      (node (ref "J12") (pin "1") (pinfunction "1_1") (pintype "passive"))
      (node (ref "J13") (pin "3") (pinfunction "3_3") (pintype "passive"))
      (node (ref "J14") (pin "6") (pinfunction "GND_6") (pintype "passive"))
      (node (ref "J14") (pin "8") (pinfunction "GND_8") (pintype "passive"))
      (node (ref "J15") (pin "5") (pinfunction "5_5") (pintype "passive"))
      (node (ref "J16") (pin "3") (pinfunction "3_3") (pintype "passive"))
      (node (ref "J17") (pin "3") (pinfunction "3_3") (pintype "passive"))
      (node (ref "J18") (pin "5") (pinfunction "5_5") (pintype "passive"))
      (node (ref "J3") (pin "5") (pinfunction "5_5") (pintype "passive"))
      (node (ref "J3") (pin "6") (pinfunction "6_6") (pintype "passive"))
      (node (ref "J3") (pin "7") (pinfunction "7_7") (pintype "passive"))
      (node (ref "J5") (pin "5") (pinfunction "5_5") (pintype "passive"))
      (node (ref "J6") (pin "5") (pinfunction "5_5") (pintype "passive"))
      (node (ref "J7") (pin "12") (pinfunction "12_12") (pintype "passive"))
      (node (ref "J7") (pin "2") (pinfunction "2_2") (pintype "passive"))
      (node (ref "J7") (pin "24") (pinfunction "24_24") (pintype "passive"))
      (node (ref "J8") (pin "1") (pinfunction "1_1") (pintype "passive"))
      (node (ref "J9") (pin "1") (pinfunction "1_1") (pintype "passive"))
      (node (ref "Q1") (pin "4") (pinfunction "4_4") (pintype "passive"))
      (node (ref "R1") (pin "2") (pinfunction "2_2") (pintype "passive"))
      (node (ref "R12") (pin "2") (pinfunction "2_2") (pintype "passive"))
      (node (ref "R25") (pin "2") (pinfunction "2_2") (pintype "passive"))
      (node (ref "R26") (pin "2") (pinfunction "2_2") (pintype "passive"))
      (node (ref "R28") (pin "2") (pinfunction "2_2") (pintype "passive"))
      (node (ref "R30") (pin "2") (pinfunction "2_2") (pintype "passive"))
      (node (ref "R31") (pin "2") (pinfunction "2_2") (pintype "passive"))
      (node (ref "R32") (pin "2") (pinfunction "2_2") (pintype "passive"))
      (node (ref "R33") (pin "2") (pinfunction "2_2") (pintype "passive"))
      (node (ref "R47") (pin "1") (pinfunction "1_1") (pintype "passive"))
      (node (ref "R50") (pin "1") (pinfunction "1_1") (pintype "passive"))
      (node (ref "R51") (pin "2") (pinfunction "2_2") (pintype "passive"))
      (node (ref "R53") (pin "1") (pinfunction "1_1") (pintype "passive"))
      (node (ref "R71") (pin "1") (pinfunction "1_1") (pintype "passive"))
      (node (ref "R73") (pin "1") (pinfunction "1_1") (pintype "passive"))
      (node (ref "S4") (pin "1") (pinfunction "1_1") (pintype "passive"))
      (node (ref "U1") (pin "3") (pinfunction "GND_3") (pintype "passive"))
      (node (ref "U2") (pin "2") (pinfunction "GND_2") (pintype "passive"))
      (node (ref "U3") (pin "2") (pinfunction "GND_2") (pintype "passive"))
      (node (ref "U4") (pin "1") (pinfunction "GND_1") (pintype "passive"))
      (node (ref "U5") (pin "2") (pinfunction "GND_2") (pintype "power_in"))
      (node (ref "U6") (pin "12") (pinfunction "VSSA_12") (pintype "power_in"))
      (node (ref "U6") (pin "18") (pinfunction "VSS_4_18") (pintype "power_in"))
      (node (ref "U6") (pin "31") (pinfunction "VSS_1_31") (pintype "passive"))
      (node (ref "U6") (pin "47") (pinfunction "VSS_2_47") (pintype "passive"))
      (node (ref "U6") (pin "63") (pinfunction "VSS_3_63") (pintype "power_in"))
      (node (ref "U7") (pin "1") (pinfunction "ADDR_1") (pintype "passive"))
      (node (ref "U7") (pin "3") (pinfunction "GND_3") (pintype "power_in"))
      (node (ref "Y1") (pin "2") (pinfunction "2_2") (pintype "passive"))
      (node (ref "Y1") (pin "4") (pinfunction "4_4") (pintype "passive"))
    )
    (net (code "60") (name "Net-(C28-Pad2)") (class "Default")
      (node (ref "C28") (pin "2") (pinfunction "2_2") (pintype "passive"))
      (node (ref "R42") (pin "1") (pinfunction "1_1") (pintype "passive"))
      (node (ref "Y1") (pin "3") (pinfunction "3_3") (pintype "passive"))
    )
    (net (code "61") (name "Net-(C30-Pad2)") (class "Default")
      (node (ref "C30") (pin "2") (pinfunction "2_2") (pintype "passive"))
      (node (ref "R43") (pin "1") (pinfunction "1_1") (pintype "passive"))
      (node (ref "Y1") (pin "1") (pinfunction "1_1") (pintype "passive"))
    )
    (net (code "62") (name "Net-(C34-Pad2)") (class "Default")
      (node (ref "C34") (pin "2") (pinfunction "2_2") (pintype "passive"))
      (node (ref "R38") (pin "2") (pinfunction "2_2") (pintype "passive"))
      (node (ref "R40") (pin "2") (pinfunction "2_2") (pintype "passive"))
      (node (ref "R49") (pin "1") (pinfunction "1_1") (pintype "passive"))
    )
    (net (code "63") (name "Net-(C47-Pad2)") (class "Default")
      (node (ref "C47") (pin "2") (pinfunction "2_2") (pintype "passive"))
      (node (ref "R60") (pin "2") (pinfunction "2_2") (pintype "passive"))
      (node (ref "R64") (pin "2") (pinfunction "2_2") (pintype "passive"))
      (node (ref "R72") (pin "1") (pinfunction "1_1") (pintype "passive"))
    )
    (net (code "64") (name "Net-(D2-K)") (class "Default")
      (node (ref "D2") (pin "2") (pinfunction "K_2") (pintype "passive"))
      (node (ref "R1") (pin "1") (pinfunction "1_1") (pintype "passive"))
    )
    (net (code "65") (name "Net-(D3-K)") (class "Default")
      (node (ref "D3") (pin "2") (pinfunction "K_2") (pintype "passive"))
      (node (ref "R12") (pin "1") (pinfunction "1_1") (pintype "passive"))
    )
    (net (code "66") (name "Net-(D4-A)") (class "Default")
      (node (ref "D4") (pin "1") (pinfunction "A_1") (pintype "passive"))
      (node (ref "Q1") (pin "1") (pinfunction "1_1") (pintype "passive"))
      (node (ref "R24") (pin "2") (pinfunction "2_2") (pintype "passive"))
    )
    (net (code "67") (name "Net-(D4-K)") (class "Default")
      (node (ref "D4") (pin "2") (pinfunction "K_2") (pintype "passive"))
      (node (ref "R26") (pin "1") (pinfunction "1_1") (pintype "passive"))
    )
    (net (code "68") (name "Net-(D5-K)") (class "Default")
      (node (ref "D5") (pin "2") (pinfunction "K_2") (pintype "passive"))
      (node (ref "R25") (pin "1") (pinfunction "1_1") (pintype "passive"))
    )
    (net (code "69") (name "Net-(J2-Sen)") (class "Default")
      (node (ref "C2") (pin "1") (pinfunction "1_1") (pintype "passive"))
      (node (ref "C4") (pin "1") (pinfunction "1_1") (pintype "passive"))
      (node (ref "J2") (pin "2") (pinfunction "Sen_2") (pintype "passive"))
      (node (ref "U1") (pin "1") (pinfunction "IN_1") (pintype "passive"))
    )
    (net (code "70") (name "Net-(J7-Pad3)") (class "Default")
      (node (ref "J7") (pin "3") (pinfunction "3_3") (pintype "passive"))
      (node (ref "R15") (pin "1") (pinfunction "1_1") (pintype "passive"))
    )
    (net (code "71") (name "Net-(J7-Pad4)") (class "Default")
      (node (ref "J7") (pin "4") (pinfunction "4_4") (pintype "passive"))
      (node (ref "R16") (pin "1") (pinfunction "1_1") (pintype "passive"))
    )
    (net (code "72") (name "Net-(J7-Pad5)") (class "Default")
      (node (ref "J7") (pin "5") (pinfunction "5_5") (pintype "passive"))
      (node (ref "R17") (pin "1") (pinfunction "1_1") (pintype "passive"))
    )
    (net (code "73") (name "Net-(J7-Pad6)") (class "Default")
      (node (ref "J7") (pin "6") (pinfunction "6_6") (pintype "passive"))
      (node (ref "R18") (pin "1") (pinfunction "1_1") (pintype "passive"))
    )
    (net (code "74") (name "Net-(J7-Pad7)") (class "Default")
      (node (ref "J7") (pin "7") (pinfunction "7_7") (pintype "passive"))
      (node (ref "R19") (pin "1") (pinfunction "1_1") (pintype "passive"))
    )
    (net (code "75") (name "Net-(J7-Pad8)") (class "Default")
      (node (ref "J7") (pin "8") (pinfunction "8_8") (pintype "passive"))
      (node (ref "R20") (pin "1") (pinfunction "1_1") (pintype "passive"))
    )
    (net (code "76") (name "Net-(J7-Pad9)") (class "Default")
      (node (ref "J7") (pin "9") (pinfunction "9_9") (pintype "passive"))
      (node (ref "R21") (pin "1") (pinfunction "1_1") (pintype "passive"))
    )
    (net (code "77") (name "Net-(J7-Pad10)") (class "Default")
      (node (ref "J7") (pin "10") (pinfunction "10_10") (pintype "passive"))
      (node (ref "R22") (pin "1") (pinfunction "1_1") (pintype "passive"))
    )
    (net (code "78") (name "Net-(J7-Pad11)") (class "Default")
      (node (ref "J7") (pin "11") (pinfunction "11_11") (pintype "passive"))
      (node (ref "R23") (pin "1") (pinfunction "1_1") (pintype "passive"))
    )
    (net (code "79") (name "Net-(J7-Pad14)") (class "Default")
      (node (ref "J7") (pin "14") (pinfunction "14_14") (pintype "passive"))
      (node (ref "R2") (pin "1") (pinfunction "1_1") (pintype "passive"))
    )
    (net (code "80") (name "Net-(J7-Pad15)") (class "Default")
      (node (ref "J7") (pin "15") (pinfunction "15_15") (pintype "passive"))
      (node (ref "R3") (pin "1") (pinfunction "1_1") (pintype "passive"))
    )
    (net (code "81") (name "Net-(J7-Pad16)") (class "Default")
      (node (ref "J7") (pin "16") (pinfunction "16_16") (pintype "passive"))
      (node (ref "R4") (pin "1") (pinfunction "1_1") (pintype "passive"))
    )
    (net (code "82") (name "Net-(J7-Pad17)") (class "Default")
      (node (ref "J7") (pin "17") (pinfunction "17_17") (pintype "passive"))
      (node (ref "R5") (pin "1") (pinfunction "1_1") (pintype "passive"))
    )
    (net (code "83") (name "Net-(J7-Pad18)") (class "Default")
      (node (ref "J7") (pin "18") (pinfunction "18_18") (pintype "passive"))
      (node (ref "R6") (pin "1") (pinfunction "1_1") (pintype "passive"))
    )
    (net (code "84") (name "Net-(J7-Pad19)") (class "Default")
      (node (ref "J7") (pin "19") (pinfunction "19_19") (pintype "passive"))
      (node (ref "R7") (pin "1") (pinfunction "1_1") (pintype "passive"))
    )
    (net (code "85") (name "Net-(J7-Pad20)") (class "Default")
      (node (ref "J7") (pin "20") (pinfunction "20_20") (pintype "passive"))
      (node (ref "R8") (pin "1") (pinfunction "1_1") (pintype "passive"))
    )
    (net (code "86") (name "Net-(J7-Pad21)") (class "Default")
      (node (ref "J7") (pin "21") (pinfunction "21_21") (pintype "passive"))
      (node (ref "R9") (pin "1") (pinfunction "1_1") (pintype "passive"))
    )
    (net (code "87") (name "Net-(J7-Pad22)") (class "Default")
      (node (ref "J7") (pin "22") (pinfunction "22_22") (pintype "passive"))
      (node (ref "R10") (pin "1") (pinfunction "1_1") (pintype "passive"))
    )
    (net (code "88") (name "Net-(J10-Pad1)") (class "Default")
      (node (ref "J10") (pin "1") (pinfunction "1_1") (pintype "passive"))
      (node (ref "R37") (pin "1") (pinfunction "1_1") (pintype "passive"))
      (node (ref "R41") (pin "1") (pinfunction "1_1") (pintype "passive"))
    )
    (net (code "89") (name "Net-(J10-Pad2)") (class "Default")
      (node (ref "J10") (pin "2") (pinfunction "2_2") (pintype "passive"))
      (node (ref "R38") (pin "1") (pinfunction "1_1") (pintype "passive"))
    )
    (net (code "90") (name "Net-(J11-OUT)") (class "Default")
      (node (ref "J11") (pin "7") (pinfunction "OUT_7") (pintype "passive"))
      (node (ref "R40") (pin "1") (pinfunction "1_1") (pintype "passive"))
    )
    (net (code "91") (name "Net-(J11-VDD)") (class "Default")
      (node (ref "C33") (pin "2") (pinfunction "2_2") (pintype "passive"))
      (node (ref "J11") (pin "5") (pinfunction "VDD_5") (pintype "passive"))
      (node (ref "R39") (pin "1") (pinfunction "1_1") (pintype "passive"))
      (node (ref "R44") (pin "1") (pinfunction "1_1") (pintype "passive"))
    )
    (net (code "92") (name "Net-(J13-Pad1)") (class "Default")
      (node (ref "J13") (pin "1") (pinfunction "1_1") (pintype "passive"))
      (node (ref "R58") (pin "1") (pinfunction "1_1") (pintype "passive"))
      (node (ref "R61") (pin "1") (pinfunction "1_1") (pintype "passive"))
    )
    (net (code "93") (name "Net-(J13-Pad2)") (class "Default")
      (node (ref "J13") (pin "2") (pinfunction "2_2") (pintype "passive"))
      (node (ref "R60") (pin "1") (pinfunction "1_1") (pintype "passive"))
    )
    (net (code "94") (name "Net-(J14-OUT)") (class "Default")
      (node (ref "J14") (pin "7") (pinfunction "OUT_7") (pintype "passive"))
      (node (ref "R64") (pin "1") (pinfunction "1_1") (pintype "passive"))
    )
    (net (code "95") (name "Net-(J14-VDD)") (class "Default")
      (node (ref "C46") (pin "2") (pinfunction "2_2") (pintype "passive"))
      (node (ref "J14") (pin "5") (pinfunction "VDD_5") (pintype "passive"))
      (node (ref "R63") (pin "1") (pinfunction "1_1") (pintype "passive"))
      (node (ref "R65") (pin "1") (pinfunction "1_1") (pintype "passive"))
    )
    (net (code "96") (name "Net-(J16-Pad4)") (class "Default")
      (node (ref "J16") (pin "4") (pinfunction "4_4") (pintype "passive"))
      (node (ref "R69") (pin "1") (pinfunction "1_1") (pintype "passive"))
    )
    (net (code "97") (name "Net-(J16-Pad5)") (class "Default")
      (node (ref "J16") (pin "5") (pinfunction "5_5") (pintype "passive"))
      (node (ref "R68") (pin "1") (pinfunction "1_1") (pintype "passive"))
    )
    (net (code "98") (name "Net-(J17-Pad4)") (class "Default")
      (node (ref "J17") (pin "4") (pinfunction "4_4") (pintype "passive"))
      (node (ref "R66") (pin "1") (pinfunction "1_1") (pintype "passive"))
    )
    (net (code "99") (name "Net-(J17-Pad5)") (class "Default")
      (node (ref "J17") (pin "5") (pinfunction "5_5") (pintype "passive"))
      (node (ref "R67") (pin "1") (pinfunction "1_1") (pintype "passive"))
    )
    (net (code "100") (name "Net-(Q1-Pad2)") (class "Default")
      (node (ref "Q1") (pin "2") (pinfunction "2_2") (pintype "passive"))
      (node (ref "Q1") (pin "3") (pinfunction "3_3") (pintype "passive"))
      (node (ref "R29") (pin "2") (pinfunction "2_2") (pintype "passive"))
      (node (ref "R31") (pin "1") (pinfunction "1_1") (pintype "passive"))
    )
    (net (code "101") (name "Net-(Q1-Pad5)") (class "Default")
      (node (ref "Q1") (pin "5") (pinfunction "5_5") (pintype "passive"))
      (node (ref "R34") (pin "2") (pinfunction "2_2") (pintype "passive"))
      (node (ref "R35") (pin "1") (pinfunction "1_1") (pintype "passive"))
    )
    (net (code "102") (name "Net-(R13-Pad1)") (class "Default")
      (node (ref "R13") (pin "1") (pinfunction "1_1") (pintype "passive"))
      (node (ref "U2") (pin "6") (pinfunction "I/O1_6") (pintype "passive"))
    )
    (net (code "103") (name "Net-(R14-Pad1)") (class "Default")
      (node (ref "R14") (pin "1") (pinfunction "1_1") (pintype "passive"))
      (node (ref "U2") (pin "4") (pinfunction "I/O2_4") (pintype "passive"))
    )
    (net (code "104") (name "Net-(R49-Pad2)") (class "Default")
      (node (ref "R49") (pin "2") (pinfunction "2_2") (pintype "passive"))
      (node (ref "R50") (pin "2") (pinfunction "2_2") (pintype "passive"))
      (node (ref "R52") (pin "1") (pinfunction "1_1") (pintype "passive"))
    )
    (net (code "105") (name "Net-(R70-Pad2)") (class "Default")
      (node (ref "R70") (pin "2") (pinfunction "2_2") (pintype "passive"))
      (node (ref "R71") (pin "2") (pinfunction "2_2") (pintype "passive"))
      (node (ref "R74") (pin "1") (pinfunction "1_1") (pintype "passive"))
    )
    (net (code "106") (name "Net-(R72-Pad2)") (class "Default")
      (node (ref "R72") (pin "2") (pinfunction "2_2") (pintype "passive"))
      (node (ref "R73") (pin "2") (pinfunction "2_2") (pintype "passive"))
      (node (ref "R75") (pin "1") (pinfunction "1_1") (pintype "passive"))
    )
    (net (code "107") (name "Net-(U3-BST)") (class "Default")
      (node (ref "C13") (pin "1") (pinfunction "1_1") (pintype "passive"))
      (node (ref "U3") (pin "1") (pinfunction "BST_1") (pintype "passive"))
    )
    (net (code "108") (name "Net-(U3-EN)") (class "Default")
      (node (ref "C8") (pin "1") (pinfunction "1_1") (pintype "passive"))
      (node (ref "R11") (pin "2") (pinfunction "2_2") (pintype "passive"))
      (node (ref "U3") (pin "4") (pinfunction "EN_4") (pintype "passive"))
    )
    (net (code "109") (name "Net-(U3-FB)") (class "Default")
      (node (ref "C15") (pin "2") (pinfunction "2_2") (pintype "passive"))
      (node (ref "R27") (pin "2") (pinfunction "2_2") (pintype "passive"))
      (node (ref "R28") (pin "1") (pinfunction "1_1") (pintype "passive"))
      (node (ref "U3") (pin "3") (pinfunction "FB_3") (pintype "passive"))
    )
    (net (code "110") (name "Net-(U3-SW)") (class "Default")
      (node (ref "C13") (pin "2") (pinfunction "2_2") (pintype "passive"))
      (node (ref "L1") (pin "1") (pinfunction "1_1") (pintype "passive"))
      (node (ref "U3") (pin "6") (pinfunction "SW_6") (pintype "passive"))
    )
    (net (code "111") (name "Net-(U5-ADD0)") (class "Default")
      (node (ref "R51") (pin "1") (pinfunction "1_1") (pintype "passive"))
      (node (ref "U5") (pin "4") (pinfunction "ADD0_4") (pintype "input"))
    )
    (net (code "112") (name "Net-(U6-BOOT0)") (class "Default")
      (node (ref "R47") (pin "2") (pinfunction "2_2") (pintype "passive"))
      (node (ref "U6") (pin "60") (pinfunction "BOOT0_60") (pintype "input"))
    )
    (net (code "113") (name "Net-(U6-NRST)") (class "Default")
      (node (ref "C29") (pin "1") (pinfunction "1_1") (pintype "passive"))
      (node (ref "R36") (pin "2") (pinfunction "2_2") (pintype "passive"))
      (node (ref "S4") (pin "2") (pinfunction "2_2") (pintype "passive"))
      (node (ref "U6") (pin "7") (pinfunction "NRST_7") (pintype "bidirectional"))
    )
    (net (code "114") (name "Net-(U6-VCAP)") (class "Default")
      (node (ref "C32") (pin "1") (pinfunction "1_1") (pintype "passive"))
      (node (ref "U6") (pin "30") (pinfunction "VCAP_30") (pintype "power_in"))
    )
    (net (code "115") (name "Net-(U7-AIN0)") (class "Default")
      (node (ref "C43") (pin "2") (pinfunction "2_2") (pintype "passive"))
      (node (ref "R52") (pin "2") (pinfunction "2_2") (pintype "passive"))
      (node (ref "U7") (pin "4") (pinfunction "AIN0_4") (pintype "passive"))
    )
    (net (code "116") (name "Net-(U7-AIN1)") (class "Default")
      (node (ref "R53") (pin "2") (pinfunction "2_2") (pintype "passive"))
      (node (ref "U7") (pin "5") (pinfunction "AIN1_5") (pintype "passive"))
    )
    (net (code "117") (name "VIN_EXT") (class "Default")
      (node (ref "C5") (pin "1") (pinfunction "1_1") (pintype "passive"))
      (node (ref "C6") (pin "1") (pinfunction "1_1") (pintype "passive"))
      (node (ref "C7") (pin "1") (pinfunction "1_1") (pintype "passive"))
      (node (ref "D1") (pin "1") (pinfunction "N-_1") (pintype "passive"))
      (node (ref "D2") (pin "1") (pinfunction "A_1") (pintype "passive"))
      (node (ref "J2") (pin "3") (pinfunction "V2_3") (pintype "passive"))
      (node (ref "R11") (pin "1") (pinfunction "1_1") (pintype "passive"))
      (node (ref "U3") (pin "5") (pinfunction "IN_5") (pintype "passive"))
    )
    (net (code "118") (name "Vbus") (class "Default")
      (node (ref "C1") (pin "1") (pinfunction "1_1") (pintype "passive"))
      (node (ref "C10") (pin "2") (pinfunction "2_2") (pintype "passive"))
      (node (ref "C3") (pin "1") (pinfunction "1_1") (pintype "passive"))
      (node (ref "J3") (pin "1") (pinfunction "1_1") (pintype "passive"))
      (node (ref "J4") (pin "1") (pinfunction "V1_1") (pintype "passive"))
      (node (ref "J5") (pin "1") (pinfunction "1_1") (pintype "passive"))
      (node (ref "R29") (pin "1") (pinfunction "1_1") (pintype "passive"))
      (node (ref "U2") (pin "5") (pinfunction "Vbus_5") (pintype "passive"))
    )
    (net (code "119") (name "unconnected-(J3-Pad4)") (class "Default")
      (node (ref "J3") (pin "4") (pinfunction "4_4") (pintype "passive+no_connect"))
    )
    (net (code "120") (name "unconnected-(J3-Pad8)") (class "Default")
      (node (ref "J3") (pin "8") (pinfunction "8_8") (pintype "passive+no_connect"))
    )
    (net (code "121") (name "unconnected-(J3-Pad9)") (class "Default")
      (node (ref "J3") (pin "9") (pinfunction "9_9") (pintype "passive+no_connect"))
    )
    (net (code "122") (name "unconnected-(J5-Pad4)") (class "Default")
      (node (ref "J5") (pin "4") (pinfunction "4_4") (pintype "passive+no_connect"))
    )
    (net (code "123") (name "unconnected-(J10-Pad4)") (class "Default")
      (node (ref "J10") (pin "4") (pinfunction "4_4") (pintype "passive"))
    )
    (net (code "124") (name "unconnected-(J10-Pad5)") (class "Default")
      (node (ref "J10") (pin "5") (pinfunction "5_5") (pintype "passive"))
    )
    (net (code "125") (name "unconnected-(J11-NC-Pad1)") (class "Default")
      (node (ref "J11") (pin "1") (pinfunction "NC_1") (pintype "passive+no_connect"))
    )
    (net (code "126") (name "unconnected-(J11-NC-Pad2)") (class "Default")
      (node (ref "J11") (pin "2") (pinfunction "NC_2") (pintype "passive+no_connect"))
    )
    (net (code "127") (name "unconnected-(J11-NC-Pad3)") (class "Default")
      (node (ref "J11") (pin "3") (pinfunction "NC_3") (pintype "passive+no_connect"))
    )
    (net (code "128") (name "unconnected-(J11-NC-Pad4)") (class "Default")
      (node (ref "J11") (pin "4") (pinfunction "NC_4") (pintype "passive+no_connect"))
    )
    (net (code "129") (name "unconnected-(J12-Pad5)") (class "Default")
      (node (ref "J12") (pin "5") (pinfunction "5_5") (pintype "passive+no_connect"))
    )
    (net (code "130") (name "unconnected-(J13-Pad4)") (class "Default")
      (node (ref "J13") (pin "4") (pinfunction "4_4") (pintype "passive"))
    )
    (net (code "131") (name "unconnected-(J13-Pad5)") (class "Default")
      (node (ref "J13") (pin "5") (pinfunction "5_5") (pintype "passive"))
    )
    (net (code "132") (name "unconnected-(J14-NC-Pad1)") (class "Default")
      (node (ref "J14") (pin "1") (pinfunction "NC_1") (pintype "passive+no_connect"))
    )
    (net (code "133") (name "unconnected-(J14-NC-Pad2)") (class "Default")
      (node (ref "J14") (pin "2") (pinfunction "NC_2") (pintype "passive+no_connect"))
    )
    (net (code "134") (name "unconnected-(J14-NC-Pad3)") (class "Default")
      (node (ref "J14") (pin "3") (pinfunction "NC_3") (pintype "passive+no_connect"))
    )
    (net (code "135") (name "unconnected-(J14-NC-Pad4)") (class "Default")
      (node (ref "J14") (pin "4") (pinfunction "NC_4") (pintype "passive+no_connect"))
    )
    (net (code "136") (name "unconnected-(R67-Pad2)") (class "Default")
      (node (ref "R67") (pin "2") (pinfunction "2_2") (pintype "passive+no_connect"))
    )
    (net (code "137") (name "unconnected-(R68-Pad2)") (class "Default")
      (node (ref "R68") (pin "2") (pinfunction "2_2") (pintype "passive+no_connect"))
    )
    (net (code "138") (name "unconnected-(U7-NC-Pad2)") (class "Default")
      (node (ref "U7") (pin "2") (pinfunction "NC_2") (pintype "passive"))
    )
    (net (code "139") (name "unconnected-(U7-NC-Pad6)") (class "Default")
      (node (ref "U7") (pin "6") (pinfunction "NC_6") (pintype "passive"))
    )
    (net (code "140") (name "unconnected-(U7-NC-Pad7)") (class "Default")
      (node (ref "U7") (pin "7") (pinfunction "NC_7") (pintype "passive"))
    )
  )
)
